# AMS_CLOCK.net
KiCad netlist of a schematic drawn in Altium Designer
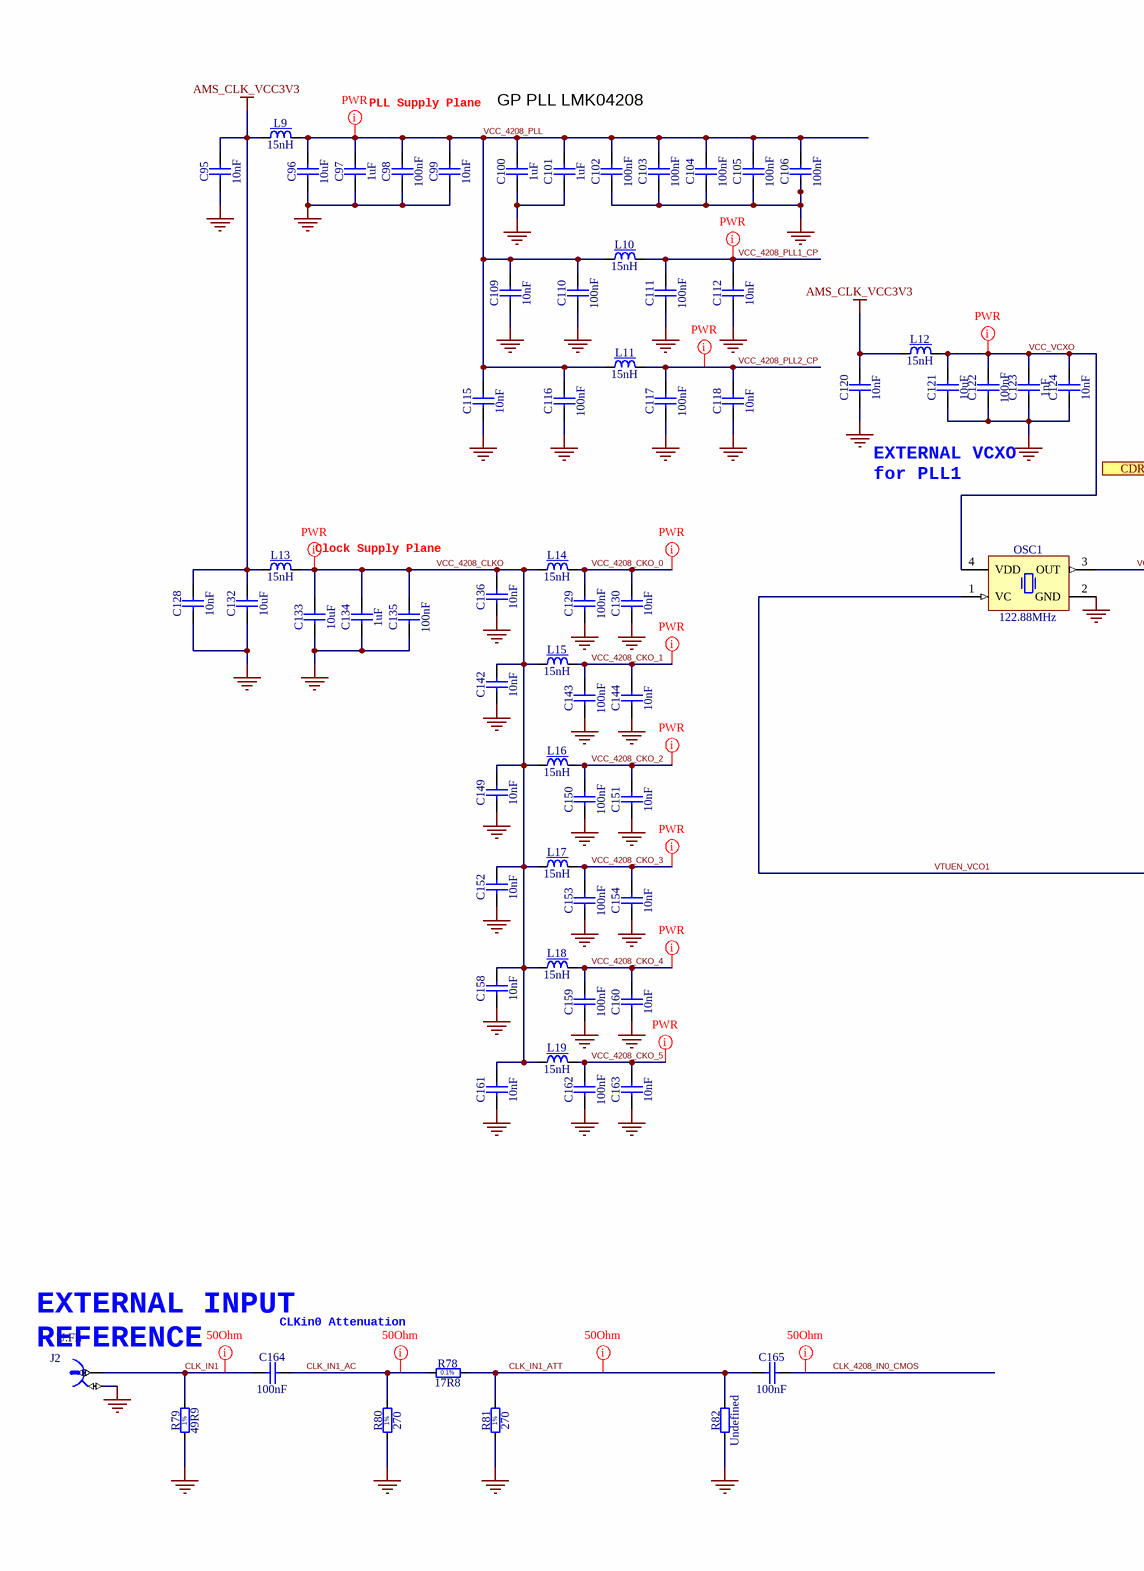
[diagram p0: AMS_CLOCK.SchDoc, left]
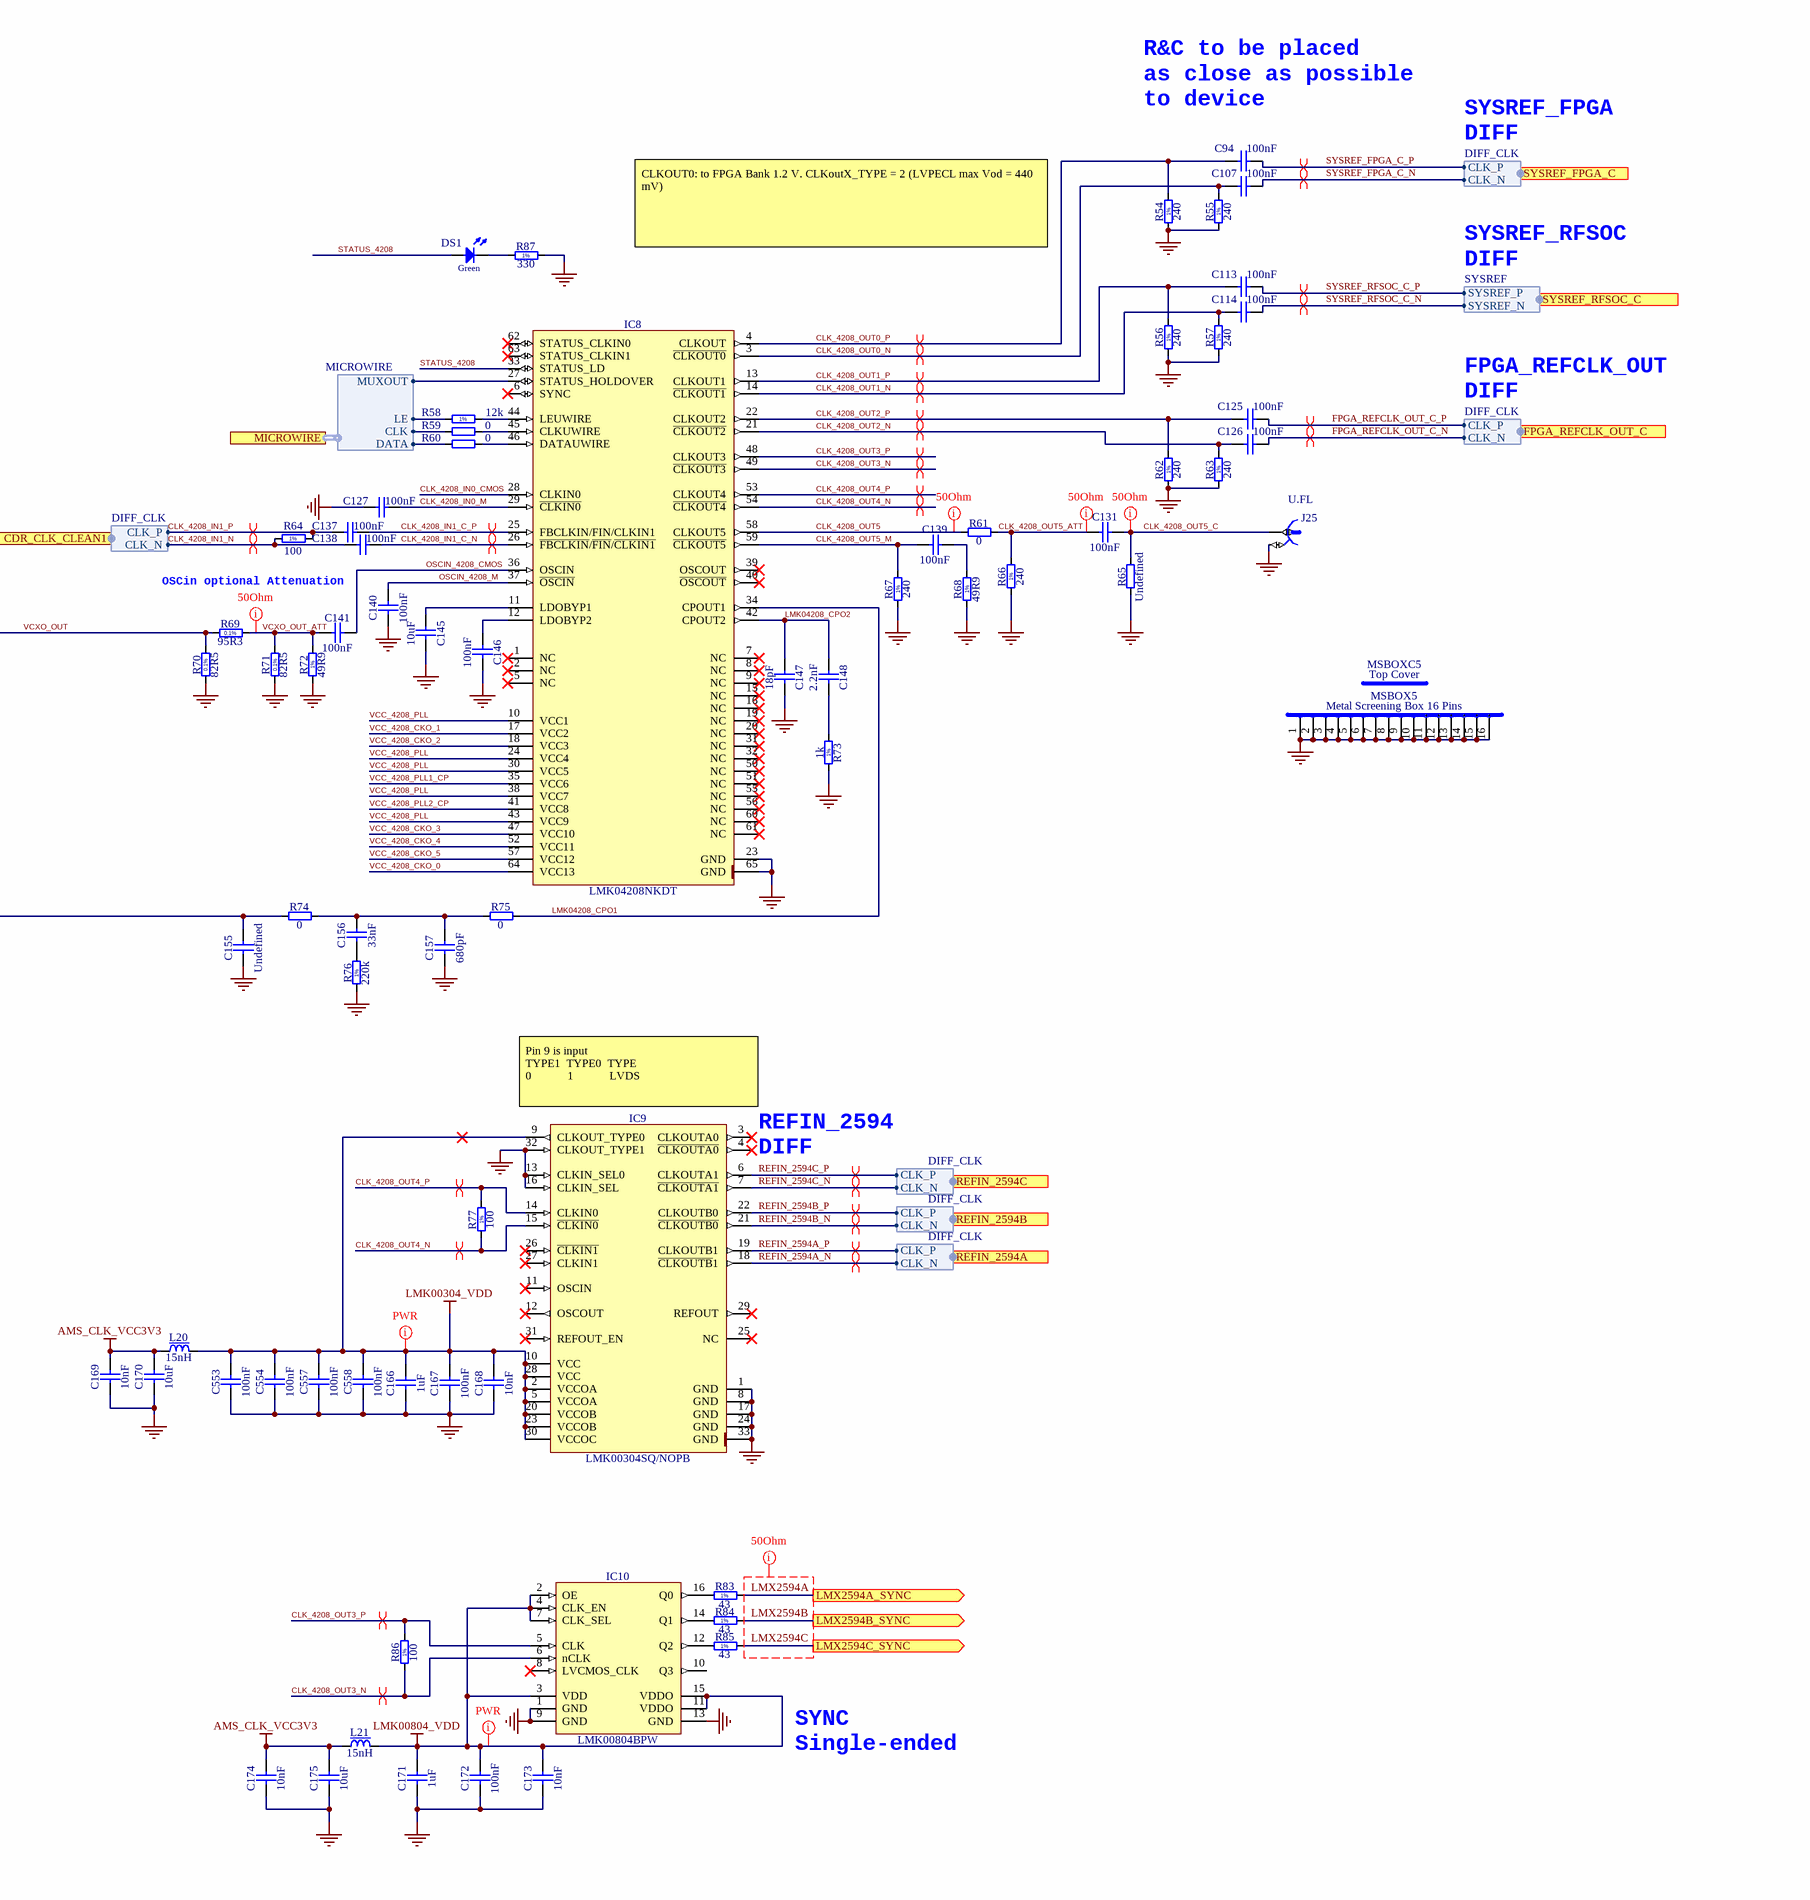
[diagram p1: AMS_CLOCK.SchDoc, right]

(export (version "E")
  (design (tool "Eeschema 10.0.6"))
  (components
    (comp (ref "C94")
      (value "100nF")
      (footprint "CAPC1005X55N")
      (description "Non-polarised capacitor")
      (fields
        (field (name "VOLTAGE") "25V")
        (field (name "TOLERANCE") "±10%")
        (field (name "AUTHOR") "CERN DEM JLC")
      )
      (libsource (lib "Capacitors") (part "Capacitor - non polarized"))
    )
    (comp (ref "C95")
      (value "10nF")
      (footprint "CAPC1005X55N")
      (description "Non-polarised capacitor")
      (fields
        (field (name "PART NUMBER") "CC0402_10NF_16V_10%_X7R")
        (field (name "VOLTAGE") "16V")
        (field (name "AUTHOR") "CERN DEM JLC")
      )
      (libsource (lib "Capacitors") (part "Capacitor - non polarized"))
    )
    (comp (ref "C96")
      (value "10uF")
      (footprint "CAPC1608X80N")
      (description "Non-polarised capacitor")
      (fields
        (field (name "PART NUMBER") "CC0603_10UF_10V_10%_X5R")
        (field (name "VOLTAGE") "10V")
        (field (name "AUTHOR") "CERN DEM JLC")
      )
      (libsource (lib "Capacitors") (part "Capacitor - non polarized"))
    )
    (comp (ref "C97")
      (value "1uF")
      (footprint "CAPC1005X55N")
      (description "Non-polarised capacitor")
      (fields
        (field (name "PART NUMBER") "CC0402_1UF_16V_10%_X5R")
        (field (name "VOLTAGE") "16V")
        (field (name "AUTHOR") "CERN DEM JLC")
      )
      (libsource (lib "Capacitors") (part "Capacitor - non polarized"))
    )
    (comp (ref "C98")
      (value "100nF")
      (footprint "CAPC1005X55N")
      (description "Non-polarised capacitor")
      (fields
        (field (name "PART NUMBER") "CC0402_100NF_25V_10%_X7R_YUDEN_TMK105B7104KVHF")
        (field (name "VOLTAGE") "25V")
        (field (name "AUTHOR") "CERN DEM JLC")
      )
      (libsource (lib "Capacitors") (part "Capacitor - non polarized"))
    )
    (comp (ref "C99")
      (value "10nF")
      (footprint "CAPC1005X55N")
      (description "Non-polarised capacitor")
      (fields
        (field (name "PART NUMBER") "CC0402_10NF_16V_10%_X7R")
        (field (name "VOLTAGE") "16V")
        (field (name "AUTHOR") "CERN DEM JLC")
      )
      (libsource (lib "Capacitors") (part "Capacitor - non polarized"))
    )
    (comp (ref "C100")
      (value "1uF")
      (footprint "CAPC1005X55N")
      (description "Non-polarised capacitor")
      (fields
        (field (name "VOLTAGE") "16V")
        (field (name "TOLERANCE") "±10%")
        (field (name "AUTHOR") "CERN DEM JLC")
      )
      (libsource (lib "Capacitors") (part "Capacitor - non polarized"))
    )
    (comp (ref "C101")
      (value "1uF")
      (footprint "CAPC1005X55N")
      (description "Non-polarised capacitor")
      (fields
        (field (name "VOLTAGE") "16V")
        (field (name "TOLERANCE") "±10%")
        (field (name "AUTHOR") "CERN DEM JLC")
      )
      (libsource (lib "Capacitors") (part "Capacitor - non polarized"))
    )
    (comp (ref "C102")
      (value "100nF")
      (footprint "CAPC1005X55N")
      (description "Non-polarised capacitor")
      (fields
        (field (name "VOLTAGE") "25V")
        (field (name "TOLERANCE") "±10%")
        (field (name "AUTHOR") "CERN DEM JLC")
      )
      (libsource (lib "Capacitors") (part "Capacitor - non polarized"))
    )
    (comp (ref "C103")
      (value "100nF")
      (footprint "CAPC1005X55N")
      (description "Non-polarised capacitor")
      (fields
        (field (name "VOLTAGE") "25V")
        (field (name "TOLERANCE") "±10%")
        (field (name "AUTHOR") "CERN DEM JLC")
      )
      (libsource (lib "Capacitors") (part "Capacitor - non polarized"))
    )
    (comp (ref "C104")
      (value "100nF")
      (footprint "CAPC1005X55N")
      (description "Non-polarised capacitor")
      (fields
        (field (name "VOLTAGE") "25V")
        (field (name "TOLERANCE") "±10%")
        (field (name "AUTHOR") "CERN DEM JLC")
      )
      (libsource (lib "Capacitors") (part "Capacitor - non polarized"))
    )
    (comp (ref "C105")
      (value "100nF")
      (footprint "CAPC1005X55N")
      (description "Non-polarised capacitor")
      (fields
        (field (name "VOLTAGE") "25V")
        (field (name "TOLERANCE") "±10%")
        (field (name "AUTHOR") "CERN DEM JLC")
      )
      (libsource (lib "Capacitors") (part "Capacitor - non polarized"))
    )
    (comp (ref "C106")
      (value "100nF")
      (footprint "CAPC1005X55N")
      (description "Non-polarised capacitor")
      (fields
        (field (name "VOLTAGE") "25V")
        (field (name "TOLERANCE") "±10%")
        (field (name "AUTHOR") "CERN DEM JLC")
      )
      (libsource (lib "Capacitors") (part "Capacitor - non polarized"))
    )
    (comp (ref "C107")
      (value "100nF")
      (footprint "CAPC1005X55N")
      (description "Non-polarised capacitor")
      (fields
        (field (name "VOLTAGE") "25V")
        (field (name "TOLERANCE") "±10%")
        (field (name "AUTHOR") "CERN DEM JLC")
      )
      (libsource (lib "Capacitors") (part "Capacitor - non polarized"))
    )
    (comp (ref "C109")
      (value "10nF")
      (footprint "CAPC1005X55N")
      (description "Non-polarised capacitor")
      (fields
        (field (name "VOLTAGE") "16V")
        (field (name "TOLERANCE") "±10%")
        (field (name "AUTHOR") "CERN DEM JLC")
      )
      (libsource (lib "Capacitors") (part "Capacitor - non polarized"))
    )
    (comp (ref "C110")
      (value "100nF")
      (footprint "CAPC1005X55N")
      (description "Non-polarised capacitor")
      (fields
        (field (name "VOLTAGE") "25V")
        (field (name "TOLERANCE") "±10%")
        (field (name "AUTHOR") "CERN DEM JLC")
      )
      (libsource (lib "Capacitors") (part "Capacitor - non polarized"))
    )
    (comp (ref "C111")
      (value "100nF")
      (footprint "CAPC1005X55N")
      (description "Non-polarised capacitor")
      (fields
        (field (name "VOLTAGE") "25V")
        (field (name "TOLERANCE") "±10%")
        (field (name "AUTHOR") "CERN DEM JLC")
      )
      (libsource (lib "Capacitors") (part "Capacitor - non polarized"))
    )
    (comp (ref "C112")
      (value "10nF")
      (footprint "CAPC1005X55N")
      (description "Non-polarised capacitor")
      (fields
        (field (name "VOLTAGE") "16V")
        (field (name "TOLERANCE") "±10%")
        (field (name "AUTHOR") "CERN DEM JLC")
      )
      (libsource (lib "Capacitors") (part "Capacitor - non polarized"))
    )
    (comp (ref "C113")
      (value "100nF")
      (footprint "CAPC1005X55N")
      (description "Non-polarised capacitor")
      (fields
        (field (name "VOLTAGE") "25V")
        (field (name "TOLERANCE") "±10%")
        (field (name "AUTHOR") "CERN DEM JLC")
      )
      (libsource (lib "Capacitors") (part "Capacitor - non polarized"))
    )
    (comp (ref "C114")
      (value "100nF")
      (footprint "CAPC1005X55N")
      (description "Non-polarised capacitor")
      (fields
        (field (name "VOLTAGE") "25V")
        (field (name "TOLERANCE") "±10%")
        (field (name "AUTHOR") "CERN DEM JLC")
      )
      (libsource (lib "Capacitors") (part "Capacitor - non polarized"))
    )
    (comp (ref "C115")
      (value "10nF")
      (footprint "CAPC1005X55N")
      (description "Non-polarised capacitor")
      (fields
        (field (name "VOLTAGE") "16V")
        (field (name "TOLERANCE") "±10%")
        (field (name "AUTHOR") "CERN DEM JLC")
      )
      (libsource (lib "Capacitors") (part "Capacitor - non polarized"))
    )
    (comp (ref "C116")
      (value "100nF")
      (footprint "CAPC1005X55N")
      (description "Non-polarised capacitor")
      (fields
        (field (name "VOLTAGE") "25V")
        (field (name "TOLERANCE") "±10%")
        (field (name "AUTHOR") "CERN DEM JLC")
      )
      (libsource (lib "Capacitors") (part "Capacitor - non polarized"))
    )
    (comp (ref "C117")
      (value "100nF")
      (footprint "CAPC1005X55N")
      (description "Non-polarised capacitor")
      (fields
        (field (name "VOLTAGE") "25V")
        (field (name "TOLERANCE") "±10%")
        (field (name "AUTHOR") "CERN DEM JLC")
      )
      (libsource (lib "Capacitors") (part "Capacitor - non polarized"))
    )
    (comp (ref "C118")
      (value "10nF")
      (footprint "CAPC1005X55N")
      (description "Non-polarised capacitor")
      (fields
        (field (name "VOLTAGE") "16V")
        (field (name "TOLERANCE") "±10%")
        (field (name "AUTHOR") "CERN DEM JLC")
      )
      (libsource (lib "Capacitors") (part "Capacitor - non polarized"))
    )
    (comp (ref "C120")
      (value "10nF")
      (footprint "CAPC1005X55N")
      (description "Non-polarised capacitor")
      (fields
        (field (name "VOLTAGE") "16V")
        (field (name "TOLERANCE") "±10%")
        (field (name "AUTHOR") "CERN DEM JLC")
      )
      (libsource (lib "Capacitors") (part "Capacitor - non polarized"))
    )
    (comp (ref "C121")
      (value "10uF")
      (footprint "CAPC1608X80N")
      (description "Non-polarised capacitor")
      (fields
        (field (name "VOLTAGE") "10V")
        (field (name "TOLERANCE") "±10%")
        (field (name "AUTHOR") "CERN DEM JLC")
      )
      (libsource (lib "Capacitors") (part "Capacitor - non polarized"))
    )
    (comp (ref "C122")
      (value "100nF")
      (footprint "CAPC1005X55N")
      (description "Non-polarised capacitor")
      (fields
        (field (name "VOLTAGE") "25V")
        (field (name "TOLERANCE") "±10%")
        (field (name "AUTHOR") "CERN DEM JLC")
      )
      (libsource (lib "Capacitors") (part "Capacitor - non polarized"))
    )
    (comp (ref "C123")
      (value "1nF")
      (footprint "CAPC1005X55N")
      (description "Non-polarised capacitor")
      (fields
        (field (name "PART NUMBER") "CC0402_1NF_50V_10%_X7R")
        (field (name "VOLTAGE") "50V")
        (field (name "AUTHOR") "CERN DEM JLC")
      )
      (libsource (lib "Capacitors") (part "Capacitor - non polarized"))
    )
    (comp (ref "C124")
      (value "10nF")
      (footprint "CAPC1005X55N")
      (description "Non-polarised capacitor")
      (fields
        (field (name "VOLTAGE") "16V")
        (field (name "TOLERANCE") "±10%")
        (field (name "AUTHOR") "CERN DEM JLC")
      )
      (libsource (lib "Capacitors") (part "Capacitor - non polarized"))
    )
    (comp (ref "C125")
      (value "100nF")
      (footprint "CAPC1005X55N")
      (description "Non-polarised capacitor")
      (fields
        (field (name "VOLTAGE") "25V")
        (field (name "TOLERANCE") "±10%")
        (field (name "AUTHOR") "CERN DEM JLC")
      )
      (libsource (lib "Capacitors") (part "Capacitor - non polarized"))
    )
    (comp (ref "C126")
      (value "100nF")
      (footprint "CAPC1005X55N")
      (description "Non-polarised capacitor")
      (fields
        (field (name "VOLTAGE") "25V")
        (field (name "TOLERANCE") "±10%")
        (field (name "AUTHOR") "CERN DEM JLC")
      )
      (libsource (lib "Capacitors") (part "Capacitor - non polarized"))
    )
    (comp (ref "C127")
      (value "100nF")
      (footprint "CAPC1005X55N")
      (description "Non-polarised capacitor")
      (fields
        (field (name "VOLTAGE") "25V")
        (field (name "TOLERANCE") "±10%")
        (field (name "AUTHOR") "CERN DEM JLC")
      )
      (libsource (lib "Capacitors") (part "Capacitor - non polarized"))
    )
    (comp (ref "C128")
      (value "10nF")
      (footprint "CAPC1005X55N")
      (description "Non-polarised capacitor")
      (fields
        (field (name "VOLTAGE") "16V")
        (field (name "TOLERANCE") "±10%")
        (field (name "AUTHOR") "CERN DEM JLC")
      )
      (libsource (lib "Capacitors") (part "Capacitor - non polarized"))
    )
    (comp (ref "C129")
      (value "100nF")
      (footprint "CAPC1005X55N")
      (description "Non-polarised capacitor")
      (fields
        (field (name "VOLTAGE") "25V")
        (field (name "TOLERANCE") "±10%")
        (field (name "AUTHOR") "CERN DEM JLC")
      )
      (libsource (lib "Capacitors") (part "Capacitor - non polarized"))
    )
    (comp (ref "C130")
      (value "10nF")
      (footprint "CAPC1005X55N")
      (description "Non-polarised capacitor")
      (fields
        (field (name "VOLTAGE") "16V")
        (field (name "TOLERANCE") "±10%")
        (field (name "AUTHOR") "CERN DEM JLC")
      )
      (libsource (lib "Capacitors") (part "Capacitor - non polarized"))
    )
    (comp (ref "C131")
      (value "100nF")
      (footprint "CAPC1005X55N")
      (description "Non-polarised capacitor")
      (fields
        (field (name "VOLTAGE") "25V")
        (field (name "TOLERANCE") "±10%")
        (field (name "AUTHOR") "CERN DEM JLC")
      )
      (libsource (lib "Capacitors") (part "Capacitor - non polarized"))
    )
    (comp (ref "C132")
      (value "10uF")
      (footprint "CAPC1608X80N")
      (description "Non-polarised capacitor")
      (fields
        (field (name "VOLTAGE") "10V")
        (field (name "TOLERANCE") "±10%")
        (field (name "AUTHOR") "CERN DEM JLC")
      )
      (libsource (lib "Capacitors") (part "Capacitor - non polarized"))
    )
    (comp (ref "C133")
      (value "10uF")
      (footprint "CAPC1608X80N")
      (description "Non-polarised capacitor")
      (fields
        (field (name "VOLTAGE") "10V")
        (field (name "TOLERANCE") "±10%")
        (field (name "AUTHOR") "CERN DEM JLC")
      )
      (libsource (lib "Capacitors") (part "Capacitor - non polarized"))
    )
    (comp (ref "C134")
      (value "1uF")
      (footprint "CAPC1005X55N")
      (description "Non-polarised capacitor")
      (fields
        (field (name "VOLTAGE") "16V")
        (field (name "TOLERANCE") "±10%")
        (field (name "AUTHOR") "CERN DEM JLC")
      )
      (libsource (lib "Capacitors") (part "Capacitor - non polarized"))
    )
    (comp (ref "C135")
      (value "100nF")
      (footprint "CAPC1005X55N")
      (description "Non-polarised capacitor")
      (fields
        (field (name "VOLTAGE") "25V")
        (field (name "TOLERANCE") "±10%")
        (field (name "AUTHOR") "CERN DEM JLC")
      )
      (libsource (lib "Capacitors") (part "Capacitor - non polarized"))
    )
    (comp (ref "C136")
      (value "10nF")
      (footprint "CAPC1005X55N")
      (description "Non-polarised capacitor")
      (fields
        (field (name "VOLTAGE") "16V")
        (field (name "TOLERANCE") "±10%")
        (field (name "AUTHOR") "CERN DEM JLC")
      )
      (libsource (lib "Capacitors") (part "Capacitor - non polarized"))
    )
    (comp (ref "C137")
      (value "100nF")
      (footprint "CAPC1005X55N")
      (description "Non-polarised capacitor")
      (fields
        (field (name "VOLTAGE") "25V")
        (field (name "TOLERANCE") "±10%")
        (field (name "AUTHOR") "CERN DEM JLC")
      )
      (libsource (lib "Capacitors") (part "Capacitor - non polarized"))
    )
    (comp (ref "C138")
      (value "100nF")
      (footprint "CAPC1005X55N")
      (description "Non-polarised capacitor")
      (fields
        (field (name "VOLTAGE") "25V")
        (field (name "TOLERANCE") "±10%")
        (field (name "AUTHOR") "CERN DEM JLC")
      )
      (libsource (lib "Capacitors") (part "Capacitor - non polarized"))
    )
    (comp (ref "C139")
      (value "100nF")
      (footprint "CAPC1005X55N")
      (description "Non-polarised capacitor")
      (fields
        (field (name "VOLTAGE") "25V")
        (field (name "TOLERANCE") "±10%")
        (field (name "AUTHOR") "CERN DEM JLC")
      )
      (libsource (lib "Capacitors") (part "Capacitor - non polarized"))
    )
    (comp (ref "C140")
      (value "100nF")
      (footprint "CAPC1005X55N")
      (description "Non-polarised capacitor")
      (fields
        (field (name "VOLTAGE") "25V")
        (field (name "TOLERANCE") "±10%")
        (field (name "AUTHOR") "CERN DEM JLC")
      )
      (libsource (lib "Capacitors") (part "Capacitor - non polarized"))
    )
    (comp (ref "C141")
      (value "100nF")
      (footprint "CAPC1005X55N")
      (description "Non-polarised capacitor")
      (fields
        (field (name "VOLTAGE") "25V")
        (field (name "TOLERANCE") "±10%")
        (field (name "AUTHOR") "CERN DEM JLC")
      )
      (libsource (lib "Capacitors") (part "Capacitor - non polarized"))
    )
    (comp (ref "C142")
      (value "10nF")
      (footprint "CAPC1005X55N")
      (description "Non-polarised capacitor")
      (fields
        (field (name "VOLTAGE") "16V")
        (field (name "TOLERANCE") "±10%")
        (field (name "AUTHOR") "CERN DEM JLC")
      )
      (libsource (lib "Capacitors") (part "Capacitor - non polarized"))
    )
    (comp (ref "C143")
      (value "100nF")
      (footprint "CAPC1005X55N")
      (description "Non-polarised capacitor")
      (fields
        (field (name "VOLTAGE") "25V")
        (field (name "TOLERANCE") "±10%")
        (field (name "AUTHOR") "CERN DEM JLC")
      )
      (libsource (lib "Capacitors") (part "Capacitor - non polarized"))
    )
    (comp (ref "C144")
      (value "10nF")
      (footprint "CAPC1005X55N")
      (description "Non-polarised capacitor")
      (fields
        (field (name "VOLTAGE") "16V")
        (field (name "TOLERANCE") "±10%")
        (field (name "AUTHOR") "CERN DEM JLC")
      )
      (libsource (lib "Capacitors") (part "Capacitor - non polarized"))
    )
    (comp (ref "C145")
      (value "10uF")
      (footprint "CAPC1608X80N")
      (description "Non-polarised capacitor")
      (fields
        (field (name "VOLTAGE") "10V")
        (field (name "TOLERANCE") "±10%")
        (field (name "AUTHOR") "CERN DEM JLC")
      )
      (libsource (lib "Capacitors") (part "Capacitor - non polarized"))
    )
    (comp (ref "C146")
      (value "100nF")
      (footprint "CAPC1005X55N")
      (description "Non-polarised capacitor")
      (fields
        (field (name "VOLTAGE") "25V")
        (field (name "TOLERANCE") "±10%")
        (field (name "AUTHOR") "CERN DEM JLC")
      )
      (libsource (lib "Capacitors") (part "Capacitor - non polarized"))
    )
    (comp (ref "C147")
      (value "18pF")
      (footprint "CAPC1005X55N")
      (description "Non-polarised capacitor")
      (fields
        (field (name "PART NUMBER") "CC0402_18PF_50V_5%_C0G")
        (field (name "VOLTAGE") "50V")
        (field (name "AUTHOR") "CERN DEM JLC")
      )
      (libsource (lib "Capacitors") (part "Capacitor - non polarized"))
    )
    (comp (ref "C148")
      (value "2.2nF")
      (footprint "CAPC1005X55N")
      (description "Non-polarised capacitor")
      (fields
        (field (name "PART NUMBER") "CC0402_2.2NF_50V_10%_X7R")
        (field (name "VOLTAGE") "50V")
        (field (name "AUTHOR") "CERN DEM JLC")
      )
      (libsource (lib "Capacitors") (part "Capacitor - non polarized"))
    )
    (comp (ref "C149")
      (value "10nF")
      (footprint "CAPC1005X55N")
      (description "Non-polarised capacitor")
      (fields
        (field (name "VOLTAGE") "16V")
        (field (name "TOLERANCE") "±10%")
        (field (name "AUTHOR") "CERN DEM JLC")
      )
      (libsource (lib "Capacitors") (part "Capacitor - non polarized"))
    )
    (comp (ref "C150")
      (value "100nF")
      (footprint "CAPC1005X55N")
      (description "Non-polarised capacitor")
      (fields
        (field (name "VOLTAGE") "25V")
        (field (name "TOLERANCE") "±10%")
        (field (name "AUTHOR") "CERN DEM JLC")
      )
      (libsource (lib "Capacitors") (part "Capacitor - non polarized"))
    )
    (comp (ref "C151")
      (value "10nF")
      (footprint "CAPC1005X55N")
      (description "Non-polarised capacitor")
      (fields
        (field (name "VOLTAGE") "16V")
        (field (name "TOLERANCE") "±10%")
        (field (name "AUTHOR") "CERN DEM JLC")
      )
      (libsource (lib "Capacitors") (part "Capacitor - non polarized"))
    )
    (comp (ref "C152")
      (value "10nF")
      (footprint "CAPC1005X55N")
      (description "Non-polarised capacitor")
      (fields
        (field (name "VOLTAGE") "16V")
        (field (name "TOLERANCE") "±10%")
        (field (name "AUTHOR") "CERN DEM JLC")
      )
      (libsource (lib "Capacitors") (part "Capacitor - non polarized"))
    )
    (comp (ref "C153")
      (value "100nF")
      (footprint "CAPC1005X55N")
      (description "Non-polarised capacitor")
      (fields
        (field (name "VOLTAGE") "25V")
        (field (name "TOLERANCE") "±10%")
        (field (name "AUTHOR") "CERN DEM JLC")
      )
      (libsource (lib "Capacitors") (part "Capacitor - non polarized"))
    )
    (comp (ref "C154")
      (value "10nF")
      (footprint "CAPC1005X55N")
      (description "Non-polarised capacitor")
      (fields
        (field (name "VOLTAGE") "16V")
        (field (name "TOLERANCE") "±10%")
        (field (name "AUTHOR") "CERN DEM JLC")
      )
      (libsource (lib "Capacitors") (part "Capacitor - non polarized"))
    )
    (comp (ref "C155")
      (value "Undefined")
      (footprint "CAPC1005X55N")
      (description "Non-polarised capacitor")
      (fields (field (name "PART NUMBER") "CC0402_NO-VALUE") (field (name "AUTHOR") "CERN DEM JLC"))
      (libsource (lib "Capacitors") (part "Capacitor - non polarized"))
    )
    (comp (ref "C156")
      (value "33nF")
      (footprint "CAPC1608X87N")
      (description "Non-polarised capacitor")
      (fields
        (field (name "VOLTAGE") "25V")
        (field (name "TOLERANCE") "±10%")
        (field (name "AUTHOR") "CERN DEM JLC")
      )
      (libsource (lib "Capacitors") (part "Capacitor - non polarized"))
    )
    (comp (ref "C157")
      (value "680pF")
      (footprint "CAPC1005X55N")
      (description "Non-polarised capacitor")
      (fields
        (field (name "PART NUMBER") "CC0402_680PF_50V_5%_X7R")
        (field (name "VOLTAGE") "50V")
        (field (name "AUTHOR") "CERN DEM JLC")
      )
      (libsource (lib "Capacitors") (part "Capacitor - non polarized"))
    )
    (comp (ref "C158")
      (value "10nF")
      (footprint "CAPC1005X55N")
      (description "Non-polarised capacitor")
      (fields
        (field (name "VOLTAGE") "16V")
        (field (name "TOLERANCE") "±10%")
        (field (name "AUTHOR") "CERN DEM JLC")
      )
      (libsource (lib "Capacitors") (part "Capacitor - non polarized"))
    )
    (comp (ref "C159")
      (value "100nF")
      (footprint "CAPC1005X55N")
      (description "Non-polarised capacitor")
      (fields
        (field (name "VOLTAGE") "25V")
        (field (name "TOLERANCE") "±10%")
        (field (name "AUTHOR") "CERN DEM JLC")
      )
      (libsource (lib "Capacitors") (part "Capacitor - non polarized"))
    )
    (comp (ref "C160")
      (value "10nF")
      (footprint "CAPC1005X55N")
      (description "Non-polarised capacitor")
      (fields
        (field (name "VOLTAGE") "16V")
        (field (name "TOLERANCE") "±10%")
        (field (name "AUTHOR") "CERN DEM JLC")
      )
      (libsource (lib "Capacitors") (part "Capacitor - non polarized"))
    )
    (comp (ref "C161")
      (value "10nF")
      (footprint "CAPC1005X55N")
      (description "Non-polarised capacitor")
      (fields
        (field (name "VOLTAGE") "16V")
        (field (name "TOLERANCE") "±10%")
        (field (name "AUTHOR") "CERN DEM JLC")
      )
      (libsource (lib "Capacitors") (part "Capacitor - non polarized"))
    )
    (comp (ref "C162")
      (value "100nF")
      (footprint "CAPC1005X55N")
      (description "Non-polarised capacitor")
      (fields
        (field (name "VOLTAGE") "25V")
        (field (name "TOLERANCE") "±10%")
        (field (name "AUTHOR") "CERN DEM JLC")
      )
      (libsource (lib "Capacitors") (part "Capacitor - non polarized"))
    )
    (comp (ref "C163")
      (value "10nF")
      (footprint "CAPC1005X55N")
      (description "Non-polarised capacitor")
      (fields
        (field (name "VOLTAGE") "16V")
        (field (name "TOLERANCE") "±10%")
        (field (name "AUTHOR") "CERN DEM JLC")
      )
      (libsource (lib "Capacitors") (part "Capacitor - non polarized"))
    )
    (comp (ref "C164")
      (value "100nF")
      (footprint "CAPC1005X55N")
      (description "Non-polarised capacitor")
      (fields
        (field (name "VOLTAGE") "25V")
        (field (name "TOLERANCE") "±10%")
        (field (name "AUTHOR") "CERN DEM JLC")
      )
      (libsource (lib "Capacitors") (part "Capacitor - non polarized"))
    )
    (comp (ref "C165")
      (value "100nF")
      (footprint "CAPC1005X55N")
      (description "Non-polarised capacitor")
      (fields
        (field (name "VOLTAGE") "25V")
        (field (name "TOLERANCE") "±10%")
        (field (name "AUTHOR") "CERN DEM JLC")
      )
      (libsource (lib "Capacitors") (part "Capacitor - non polarized"))
    )
    (comp (ref "C166")
      (value "1uF")
      (footprint "CAPC1005X55N")
      (description "Non-polarised capacitor")
      (fields
        (field (name "VOLTAGE") "16V")
        (field (name "TOLERANCE") "±10%")
        (field (name "AUTHOR") "CERN DEM JLC")
      )
      (libsource (lib "Capacitors") (part "Capacitor - non polarized"))
    )
    (comp (ref "C167")
      (value "100nF")
      (footprint "CAPC1005X55N")
      (description "Non-polarised capacitor")
      (fields
        (field (name "VOLTAGE") "25V")
        (field (name "TOLERANCE") "±10%")
        (field (name "AUTHOR") "CERN DEM JLC")
      )
      (libsource (lib "Capacitors") (part "Capacitor - non polarized"))
    )
    (comp (ref "C168")
      (value "10nF")
      (footprint "CAPC1005X55N")
      (description "Non-polarised capacitor")
      (fields
        (field (name "VOLTAGE") "16V")
        (field (name "TOLERANCE") "±10%")
        (field (name "AUTHOR") "CERN DEM JLC")
      )
      (libsource (lib "Capacitors") (part "Capacitor - non polarized"))
    )
    (comp (ref "C169")
      (value "10nF")
      (footprint "CAPC1005X55N")
      (description "Non-polarised capacitor")
      (fields
        (field (name "VOLTAGE") "16V")
        (field (name "TOLERANCE") "±10%")
        (field (name "AUTHOR") "CERN DEM JLC")
      )
      (libsource (lib "Capacitors") (part "Capacitor - non polarized"))
    )
    (comp (ref "C170")
      (value "10uF")
      (footprint "CAPC1608X80N")
      (description "Non-polarised capacitor")
      (fields
        (field (name "VOLTAGE") "10V")
        (field (name "TOLERANCE") "±10%")
        (field (name "AUTHOR") "CERN DEM JLC")
      )
      (libsource (lib "Capacitors") (part "Capacitor - non polarized"))
    )
    (comp (ref "C171")
      (value "1uF")
      (footprint "CAPC1005X55N")
      (description "Non-polarised capacitor")
      (fields
        (field (name "VOLTAGE") "16V")
        (field (name "TOLERANCE") "±10%")
        (field (name "AUTHOR") "CERN DEM JLC")
      )
      (libsource (lib "Capacitors") (part "Capacitor - non polarized"))
    )
    (comp (ref "C172")
      (value "100nF")
      (footprint "CAPC1005X55N")
      (description "Non-polarised capacitor")
      (fields
        (field (name "VOLTAGE") "25V")
        (field (name "TOLERANCE") "±10%")
        (field (name "AUTHOR") "CERN DEM JLC")
      )
      (libsource (lib "Capacitors") (part "Capacitor - non polarized"))
    )
    (comp (ref "C173")
      (value "10nF")
      (footprint "CAPC1005X55N")
      (description "Non-polarised capacitor")
      (fields
        (field (name "VOLTAGE") "16V")
        (field (name "TOLERANCE") "±10%")
        (field (name "AUTHOR") "CERN DEM JLC")
      )
      (libsource (lib "Capacitors") (part "Capacitor - non polarized"))
    )
    (comp (ref "C174")
      (value "10nF")
      (footprint "CAPC1005X55N")
      (description "Non-polarised capacitor")
      (fields
        (field (name "VOLTAGE") "16V")
        (field (name "TOLERANCE") "±10%")
        (field (name "AUTHOR") "CERN DEM JLC")
      )
      (libsource (lib "Capacitors") (part "Capacitor - non polarized"))
    )
    (comp (ref "C175")
      (value "10uF")
      (footprint "CAPC1608X80N")
      (description "Non-polarised capacitor")
      (fields
        (field (name "VOLTAGE") "10V")
        (field (name "TOLERANCE") "±10%")
        (field (name "AUTHOR") "CERN DEM JLC")
      )
      (libsource (lib "Capacitors") (part "Capacitor - non polarized"))
    )
    (comp (ref "C553")
      (value "100nF")
      (footprint "CAPC1005X55N")
      (description "Non-polarised capacitor")
      (fields
        (field (name "VOLTAGE") "25V")
        (field (name "TOLERANCE") "±10%")
        (field (name "AUTHOR") "CERN DEM JLC")
      )
      (libsource (lib "Capacitors") (part "Capacitor - non polarized"))
    )
    (comp (ref "C554")
      (value "100nF")
      (footprint "CAPC1005X55N")
      (description "Non-polarised capacitor")
      (fields
        (field (name "VOLTAGE") "25V")
        (field (name "TOLERANCE") "±10%")
        (field (name "AUTHOR") "CERN DEM JLC")
      )
      (libsource (lib "Capacitors") (part "Capacitor - non polarized"))
    )
    (comp (ref "C557")
      (value "100nF")
      (footprint "CAPC1005X55N")
      (description "Non-polarised capacitor")
      (fields
        (field (name "VOLTAGE") "25V")
        (field (name "TOLERANCE") "±10%")
        (field (name "AUTHOR") "CERN DEM JLC")
      )
      (libsource (lib "Capacitors") (part "Capacitor - non polarized"))
    )
    (comp (ref "C558")
      (value "100nF")
      (footprint "CAPC1005X55N")
      (description "Non-polarised capacitor")
      (fields
        (field (name "VOLTAGE") "25V")
        (field (name "TOLERANCE") "±10%")
        (field (name "AUTHOR") "CERN DEM JLC")
      )
      (libsource (lib "Capacitors") (part "Capacitor - non polarized"))
    )
    (comp (ref "DS1")
      (value "Green")
      (footprint "LED_OSRAM_LGL29K")
      (description "LED Green 1C 2A")
      (fields
        (field (name "PART NUMBER") "LED_OSRAM_LG L29K-G2J1-24-Z")
        (field (name "MANUFACTURER") "OSRAM")
        (field (name "AUTHOR") "CERN DEM JLC")
      )
      (libsource (lib "ICs And Semiconductors") (part "LED Green 1C 2A"))
    )
    (comp (ref "IC8")
      (value "LMK04208NKDT")
      (footprint "QFN50P900X900X80-65N-S730")
      (description "Low-Noise Clock Jitter Cleaner with Dual Loop PLLs")
      (fields (field (name "MANUFACTURER") "TEXAS INSTRUMENTS") (field (name "AUTHOR") "CERN DEM JLC"))
      (libsource (lib "ICs And Semiconductors") (part "LMK04208"))
    )
    (comp (ref "IC9")
      (value "LMK00304SQ/NOPB")
      (footprint "QFN50P500X500X80-33N-S320")
      (description "3-GHz 4-Output Ultra-Low Additive Jitter Differential Clock Buffer/Level Translator")
      (fields (field (name "MANUFACTURER") "TEXAS INSTRUMENTS") (field (name "AUTHOR") "CERN DEM JLC"))
      (libsource (lib "ICs And Semiconductors") (part "LMK00304"))
    )
    (comp (ref "IC10")
      (value "LMK00804BPW")
      (footprint "SOP65P640X120-16N")
      (description "Low Skew, 1-to-4 Multiplexed Differential/LVCMOS-to-LVCMOS/TTL Fanout Buffer")
      (fields (field (name "MANUFACTURER") "TEXAS INSTRUMENTS") (field (name "AUTHOR") "CERN DEM JLC"))
      (libsource (lib "ICs And Semiconductors") (part "LMK00804B"))
    )
    (comp (ref "J2")
      (value "U.FL")
      (footprint "HIROSE_U.FL-R-SMT-1(10)")
      (fields
        (field (name "MANUFACTURER PART NUMBER") "U.FL-R-SMT-1(10)")
        (field (name "MANUFACTURER") "HIROSE (HRS)")
        (field (name "PART NUMBER") "HIROSE_U.FL-R-SMT-1(10)")
        (field (name "AUTHOR") "CERN DEM JLC")
      )
      (libsource (lib "") (part "Coax_1Male_1Shield_1"))
    )
    (comp (ref "J25")
      (value "U.FL")
      (footprint "HIROSE_U.FL-R-SMT-1(10)")
      (fields
        (field (name "MANUFACTURER PART NUMBER") "U.FL-R-SMT-1(10)")
        (field (name "MANUFACTURER") "HIROSE (HRS)")
        (field (name "PART NUMBER") "HIROSE_U.FL-R-SMT-1(10)")
        (field (name "AUTHOR") "CERN DEM JLC")
      )
      (libsource (lib "Connectors") (part "Coax_1Male_1Shield"))
    )
    (comp (ref "L9")
      (value "15nH")
      (footprint "IND_COILCRAFT_0402DC")
      (description "Inductor With Core")
      (fields
        (field (name "PART NUMBER") "IND0402_15NH_2%_COILCRAFT_0402DC")
        (field (name "POWER") "1A")
        (field (name "AUTHOR") "CERN DEM JLC")
      )
      (libsource (lib "Inductors & Transformers") (part "Inductor With Magnetic core"))
    )
    (comp (ref "L10")
      (value "15nH")
      (footprint "IND_COILCRAFT_0402DC")
      (description "Inductor With Core")
      (fields
        (field (name "TOLERANCE") "±2%")
        (field (name "PART NUMBER") "IND0402_15NH_2%_COILCRAFT_0402DC")
        (field (name "AUTHOR") "CERN DEM JLC")
      )
      (libsource (lib "Inductors & Transformers") (part "Inductor With Magnetic core"))
    )
    (comp (ref "L11")
      (value "15nH")
      (footprint "IND_COILCRAFT_0402DC")
      (description "Inductor With Core")
      (fields
        (field (name "TOLERANCE") "±2%")
        (field (name "PART NUMBER") "IND0402_15NH_2%_COILCRAFT_0402DC")
        (field (name "AUTHOR") "CERN DEM JLC")
      )
      (libsource (lib "Inductors & Transformers") (part "Inductor With Magnetic core"))
    )
    (comp (ref "L12")
      (value "15nH")
      (footprint "IND_COILCRAFT_0402DC")
      (description "Inductor With Core")
      (fields
        (field (name "TOLERANCE") "±2%")
        (field (name "PART NUMBER") "IND0402_15NH_2%_COILCRAFT_0402DC")
        (field (name "AUTHOR") "CERN DEM JLC")
      )
      (libsource (lib "Inductors & Transformers") (part "Inductor With Magnetic core"))
    )
    (comp (ref "L13")
      (value "15nH")
      (footprint "IND_COILCRAFT_0402DC")
      (description "Inductor With Core")
      (fields
        (field (name "TOLERANCE") "±2%")
        (field (name "PART NUMBER") "IND0402_15NH_2%_COILCRAFT_0402DC")
        (field (name "AUTHOR") "CERN DEM JLC")
      )
      (libsource (lib "Inductors & Transformers") (part "Inductor With Magnetic core"))
    )
    (comp (ref "L14")
      (value "15nH")
      (footprint "IND_COILCRAFT_0402DC")
      (description "Inductor With Core")
      (fields
        (field (name "TOLERANCE") "±2%")
        (field (name "PART NUMBER") "IND0402_15NH_2%_COILCRAFT_0402DC")
        (field (name "AUTHOR") "CERN DEM JLC")
      )
      (libsource (lib "Inductors & Transformers") (part "Inductor With Magnetic core"))
    )
    (comp (ref "L15")
      (value "15nH")
      (footprint "IND_COILCRAFT_0402DC")
      (description "Inductor With Core")
      (fields
        (field (name "TOLERANCE") "±2%")
        (field (name "PART NUMBER") "IND0402_15NH_2%_COILCRAFT_0402DC")
        (field (name "AUTHOR") "CERN DEM JLC")
      )
      (libsource (lib "Inductors & Transformers") (part "Inductor With Magnetic core"))
    )
    (comp (ref "L16")
      (value "15nH")
      (footprint "IND_COILCRAFT_0402DC")
      (description "Inductor With Core")
      (fields
        (field (name "TOLERANCE") "±2%")
        (field (name "PART NUMBER") "IND0402_15NH_2%_COILCRAFT_0402DC")
        (field (name "AUTHOR") "CERN DEM JLC")
      )
      (libsource (lib "Inductors & Transformers") (part "Inductor With Magnetic core"))
    )
    (comp (ref "L17")
      (value "15nH")
      (footprint "IND_COILCRAFT_0402DC")
      (description "Inductor With Core")
      (fields
        (field (name "TOLERANCE") "±2%")
        (field (name "PART NUMBER") "IND0402_15NH_2%_COILCRAFT_0402DC")
        (field (name "AUTHOR") "CERN DEM JLC")
      )
      (libsource (lib "Inductors & Transformers") (part "Inductor With Magnetic core"))
    )
    (comp (ref "L18")
      (value "15nH")
      (footprint "IND_COILCRAFT_0402DC")
      (description "Inductor With Core")
      (fields
        (field (name "TOLERANCE") "±2%")
        (field (name "PART NUMBER") "IND0402_15NH_2%_COILCRAFT_0402DC")
        (field (name "AUTHOR") "CERN DEM JLC")
      )
      (libsource (lib "Inductors & Transformers") (part "Inductor With Magnetic core"))
    )
    (comp (ref "L19")
      (value "15nH")
      (footprint "IND_COILCRAFT_0402DC")
      (description "Inductor With Core")
      (fields
        (field (name "TOLERANCE") "±2%")
        (field (name "PART NUMBER") "IND0402_15NH_2%_COILCRAFT_0402DC")
        (field (name "AUTHOR") "CERN DEM JLC")
      )
      (libsource (lib "Inductors & Transformers") (part "Inductor With Magnetic core"))
    )
    (comp (ref "L20")
      (value "15nH")
      (footprint "IND_COILCRAFT_0402DC")
      (description "Inductor With Core")
      (fields
        (field (name "TOLERANCE") "±2%")
        (field (name "PART NUMBER") "IND0402_15NH_2%_COILCRAFT_0402DC")
        (field (name "AUTHOR") "CERN DEM JLC")
      )
      (libsource (lib "Inductors & Transformers") (part "Inductor With Magnetic core"))
    )
    (comp (ref "L21")
      (value "15nH")
      (footprint "IND_COILCRAFT_0402DC")
      (description "Inductor With Core")
      (fields
        (field (name "TOLERANCE") "±2%")
        (field (name "PART NUMBER") "IND0402_15NH_2%_COILCRAFT_0402DC")
        (field (name "AUTHOR") "CERN DEM JLC")
      )
      (libsource (lib "Inductors & Transformers") (part "Inductor With Magnetic core"))
    )
    (comp (ref "MSBOX5")
      (value "Metal Screening Box 16 Pins")
      (footprint "MSBOX_LEADERTECH_SMS-254-F")
      (fields
        (field (name "PART NUMBER") "MSBOX_LEADERTECH_SMS-254-F")
        (field (name "MANUFACTURER") "LEADERTECH")
        (field (name "MANUFACTURER PART NUMBER") "SMS-254-F")
        (field (name "AUTHOR") "CERN DEM BC")
      )
      (libsource (lib "Eletro-mechanical") (part "Metal Screening Box - 16 pins"))
    )
    (comp (ref "MSBOXC5")
      (value "Top Cover")
      (footprint "MSBOX_LEADERTECH_SMS-254-C")
      (description "Metal Screening Box - Top Cover 0 Pin")
      (fields
        (field (name "PART NUMBER") "MSBOX_LEADERTECH_SMS-254-C")
        (field (name "MANUFACTURER") "LEADERTECH")
        (field (name "AUTHOR") "CERN DEM BC")
      )
      (libsource (lib "Eletro-mechanical") (part "Metal Screening Box - Top Cover"))
    )
    (comp (ref "OSC1")
      (value "122.88MHz")
      (footprint "OSC_CRYSTEK_CVHD-950")
      (description "Oscillator 4 pins 1=VC 2=GND 3=OUT 4=VDD")
      (fields
        (field (name "PART NUMBER") "OSC_122.88MHZ_CRYSTEK_CVHD-950-122.880")
        (field (name "MANUFACTURER") "CRYSTEK CRYSTAL")
        (field (name "AUTHOR") "CERN DEM JLC")
      )
      (libsource (lib "ICs And Semiconductors") (part "Oscillator 1VC 2GND 3OUT 4VDD"))
    )
    (comp (ref "R54")
      (value "240")
      (footprint "RESC1005X40N")
      (description "Resistor - 1%")
      (fields
        (field (name "POWER") "0.0625W")
        (field (name "TOLERANCE") "±1%")
        (field (name "AUTHOR") "CERN DEM JLC")
      )
      (libsource (lib "Resistors") (part "Resistor - 1%"))
    )
    (comp (ref "R55")
      (value "240")
      (footprint "RESC1005X40N")
      (description "Resistor - 1%")
      (fields
        (field (name "POWER") "0.0625W")
        (field (name "TOLERANCE") "±1%")
        (field (name "AUTHOR") "CERN DEM JLC")
      )
      (libsource (lib "Resistors") (part "Resistor - 1%"))
    )
    (comp (ref "R56")
      (value "240")
      (footprint "RESC1005X40N")
      (description "Resistor - 1%")
      (fields
        (field (name "TOLERANCE") "±1%")
        (field (name "POWER") "0.0625W")
        (field (name "AUTHOR") "CERN DEM JLC")
      )
      (libsource (lib "Resistors") (part "Resistor - 1%"))
    )
    (comp (ref "R57")
      (value "240")
      (footprint "RESC1005X40N")
      (description "Resistor - 1%")
      (fields
        (field (name "TOLERANCE") "±1%")
        (field (name "POWER") "0.0625W")
        (field (name "AUTHOR") "CERN DEM JLC")
      )
      (libsource (lib "Resistors") (part "Resistor - 1%"))
    )
    (comp (ref "R58")
      (value "12k")
      (footprint "RESC1005X40N")
      (description "Resistor - 1%")
      (fields
        (field (name "PART NUMBER") "R0402_12K_1%_0.0625W_100PPM")
        (field (name "POWER") "0.0625W")
        (field (name "AUTHOR") "CERN DEM JLC")
      )
      (libsource (lib "Resistors") (part "Resistor - 1%"))
    )
    (comp (ref "R59")
      (value "0")
      (footprint "RESC1005X40N")
      (description "Resistor")
      (fields
        (field (name "PART NUMBER") "R0402_0R_JUMPER")
        (field (name "MANUFACTURER") "GENERIC")
        (field (name "AUTHOR") "CERN DEM JLC")
      )
      (libsource (lib "Resistors") (part "Resistor"))
    )
    (comp (ref "R60")
      (value "0")
      (footprint "RESC1005X40N")
      (description "Resistor")
      (fields
        (field (name "PART NUMBER") "R0402_0R_JUMPER")
        (field (name "MANUFACTURER") "GENERIC")
        (field (name "AUTHOR") "CERN DEM JLC")
      )
      (libsource (lib "Resistors") (part "Resistor"))
    )
    (comp (ref "R61")
      (value "0")
      (footprint "RESC1005X40N")
      (description "Resistor")
      (fields
        (field (name "PART NUMBER") "R0402_0R_JUMPER")
        (field (name "MANUFACTURER") "GENERIC")
        (field (name "AUTHOR") "CERN DEM JLC")
      )
      (libsource (lib "Resistors") (part "Resistor"))
    )
    (comp (ref "R62")
      (value "240")
      (footprint "RESC1005X40N")
      (description "Resistor - 1%")
      (fields
        (field (name "TOLERANCE") "±1%")
        (field (name "POWER") "0.0625W")
        (field (name "AUTHOR") "CERN DEM JLC")
      )
      (libsource (lib "Resistors") (part "Resistor - 1%"))
    )
    (comp (ref "R63")
      (value "240")
      (footprint "RESC1005X40N")
      (description "Resistor - 1%")
      (fields
        (field (name "TOLERANCE") "±1%")
        (field (name "POWER") "0.0625W")
        (field (name "AUTHOR") "CERN DEM JLC")
      )
      (libsource (lib "Resistors") (part "Resistor - 1%"))
    )
    (comp (ref "R64")
      (value "100")
      (footprint "RESC1005X40N")
      (description "Resistor - 1%")
      (fields
        (field (name "PART NUMBER") "R0402_100R_1%_0.0625W_100PPM")
        (field (name "POWER") "0.0625W")
        (field (name "AUTHOR") "CERN DEM JLC")
      )
      (libsource (lib "Resistors") (part "Resistor - 1%"))
    )
    (comp (ref "R65")
      (value "Undefined")
      (footprint "RESC1005X40N")
      (description "Resistor")
      (fields (field (name "PART NUMBER") "R0402_NO-VALUE") (field (name "AUTHOR") "CERN DEM JLC"))
      (libsource (lib "Resistors") (part "Resistor"))
    )
    (comp (ref "R66")
      (value "240")
      (footprint "RESC1005X40N")
      (description "Resistor - 1%")
      (fields
        (field (name "TOLERANCE") "±1%")
        (field (name "POWER") "0.0625W")
        (field (name "AUTHOR") "CERN DEM JLC")
      )
      (libsource (lib "Resistors") (part "Resistor - 1%"))
    )
    (comp (ref "R67")
      (value "240")
      (footprint "RESC1005X40N")
      (description "Resistor - 1%")
      (fields
        (field (name "TOLERANCE") "±1%")
        (field (name "POWER") "0.0625W")
        (field (name "AUTHOR") "CERN DEM JLC")
      )
      (libsource (lib "Resistors") (part "Resistor - 1%"))
    )
    (comp (ref "R68")
      (value "49R9")
      (footprint "RESC1005X40N")
      (description "Resistor - 1%")
      (fields
        (field (name "PART NUMBER") "R0402_49R9_1%_0.0625W_100PPM")
        (field (name "POWER") "0.0625W")
        (field (name "AUTHOR") "CERN DEM JLC")
      )
      (libsource (lib "Resistors") (part "Resistor - 1%"))
    )
    (comp (ref "R69")
      (value "95R3")
      (footprint "RESC1608X55N")
      (description "Resistor - 0.1%")
      (fields
        (field (name "PART NUMBER") "R0603_95R3_0.1%_0.063W_10PPM")
        (field (name "POWER") "0.063W")
        (field (name "AUTHOR") "CERN DEM JLC")
      )
      (libsource (lib "Resistors") (part "Resistor - 0.1%"))
    )
    (comp (ref "R70")
      (value "82R5")
      (footprint "RESC1608X55N")
      (description "Resistor - 0.1%")
      (fields
        (field (name "PART NUMBER") "R0603_82R5_0.1%_0.063W_10PPM")
        (field (name "POWER") "0.063W")
        (field (name "AUTHOR") "CERN DEM JLC")
      )
      (libsource (lib "Resistors") (part "Resistor - 0.1%"))
    )
    (comp (ref "R71")
      (value "82R5")
      (footprint "RESC1608X55N")
      (description "Resistor - 0.1%")
      (fields
        (field (name "PART NUMBER") "R0603_82R5_0.1%_0.063W_10PPM")
        (field (name "POWER") "0.063W")
        (field (name "AUTHOR") "CERN DEM JLC")
      )
      (libsource (lib "Resistors") (part "Resistor - 0.1%"))
    )
    (comp (ref "R72")
      (value "49R9")
      (footprint "RESC1005X40N")
      (description "Resistor - 1%")
      (fields
        (field (name "PART NUMBER") "R0402_49R9_1%_0.0625W_100PPM")
        (field (name "POWER") "0.0625W")
        (field (name "AUTHOR") "CERN DEM JLC")
      )
      (libsource (lib "Resistors") (part "Resistor - 1%"))
    )
    (comp (ref "R73")
      (value "1k")
      (footprint "RESC1005X40N")
      (description "Resistor - 1%")
      (fields
        (field (name "PART NUMBER") "R0402_1K_1%_0.0625W_100PPM")
        (field (name "POWER") "0.0625W")
        (field (name "AUTHOR") "CERN DEM JLC")
      )
      (libsource (lib "Resistors") (part "Resistor - 1%"))
    )
    (comp (ref "R74")
      (value "0")
      (footprint "RESC1005X40N")
      (description "Resistor")
      (fields
        (field (name "PART NUMBER") "R0402_0R_JUMPER")
        (field (name "MANUFACTURER") "GENERIC")
        (field (name "AUTHOR") "CERN DEM JLC")
      )
      (libsource (lib "Resistors") (part "Resistor"))
    )
    (comp (ref "R75")
      (value "0")
      (footprint "RESC1005X40N")
      (description "Resistor")
      (fields
        (field (name "PART NUMBER") "R0402_0R_JUMPER")
        (field (name "MANUFACTURER") "GENERIC")
        (field (name "AUTHOR") "CERN DEM JLC")
      )
      (libsource (lib "Resistors") (part "Resistor"))
    )
    (comp (ref "R76")
      (value "220k")
      (footprint "RESC1005X40N")
      (description "Resistor - 1%")
      (fields
        (field (name "PART NUMBER") "R0402_220K_1%_0.0625W_100PPM")
        (field (name "POWER") "0.0625W")
        (field (name "AUTHOR") "CERN DEM JLC")
      )
      (libsource (lib "Resistors") (part "Resistor - 1%"))
    )
    (comp (ref "R77")
      (value "100")
      (footprint "RESC1005X40N")
      (description "Resistor - 1%")
      (fields
        (field (name "PART NUMBER") "R0402_100R_1%_0.0625W_100PPM")
        (field (name "POWER") "0.0625W")
        (field (name "AUTHOR") "CERN DEM JLC")
      )
      (libsource (lib "Resistors") (part "Resistor - 1%"))
    )
    (comp (ref "R78")
      (value "17R8")
      (footprint "RESC1608X55N")
      (description "Resistor - 0.1%")
      (fields
        (field (name "PART NUMBER") "R0603_17R8_0.1%_0.063W_10PPM")
        (field (name "POWER") "0.063W")
        (field (name "AUTHOR") "CERN DEM JLC")
      )
      (libsource (lib "Resistors") (part "Resistor - 0.1%"))
    )
    (comp (ref "R79")
      (value "49R9")
      (footprint "RESC1005X40N")
      (description "Resistor - 1%")
      (fields
        (field (name "PART NUMBER") "R0402_49R9_1%_0.0625W_100PPM")
        (field (name "POWER") "0.0625W")
        (field (name "AUTHOR") "CERN DEM JLC")
      )
      (libsource (lib "Resistors") (part "Resistor - 1%"))
    )
    (comp (ref "R80")
      (value "270")
      (footprint "RESC1005X40N")
      (description "Resistor - 1%")
      (fields
        (field (name "PART NUMBER") "R0402_270R_1%_0.0625W_100PPM")
        (field (name "POWER") "0.0625W")
        (field (name "AUTHOR") "CERN DEM JLC")
      )
      (libsource (lib "Resistors") (part "Resistor - 1%"))
    )
    (comp (ref "R81")
      (value "270")
      (footprint "RESC1005X40N")
      (description "Resistor - 1%")
      (fields
        (field (name "PART NUMBER") "R0402_270R_1%_0.0625W_100PPM")
        (field (name "POWER") "0.0625W")
        (field (name "AUTHOR") "CERN DEM JLC")
      )
      (libsource (lib "Resistors") (part "Resistor - 1%"))
    )
    (comp (ref "R82")
      (value "Undefined")
      (footprint "RESC1005X40N")
      (description "Resistor")
      (fields (field (name "PART NUMBER") "R0402_NO-VALUE") (field (name "AUTHOR") "CERN DEM JLC"))
      (libsource (lib "Resistors") (part "Resistor"))
    )
    (comp (ref "R83")
      (value "43")
      (footprint "RESC1005X40N")
      (description "Resistor - 1%")
      (fields
        (field (name "PART NUMBER") "R0402_43R_1%_0.0625W_100PPM")
        (field (name "POWER") "0.0625W")
        (field (name "AUTHOR") "CERN DEM JLC")
      )
      (libsource (lib "Resistors") (part "Resistor - 1%"))
    )
    (comp (ref "R84")
      (value "43")
      (footprint "RESC1005X40N")
      (description "Resistor - 1%")
      (fields
        (field (name "PART NUMBER") "R0402_43R_1%_0.0625W_100PPM")
        (field (name "POWER") "0.0625W")
        (field (name "AUTHOR") "CERN DEM JLC")
      )
      (libsource (lib "Resistors") (part "Resistor - 1%"))
    )
    (comp (ref "R85")
      (value "43")
      (footprint "RESC1005X40N")
      (description "Resistor - 1%")
      (fields
        (field (name "PART NUMBER") "R0402_43R_1%_0.0625W_100PPM")
        (field (name "POWER") "0.0625W")
        (field (name "AUTHOR") "CERN DEM JLC")
      )
      (libsource (lib "Resistors") (part "Resistor - 1%"))
    )
    (comp (ref "R86")
      (value "100")
      (footprint "RESC1005X40N")
      (description "Resistor - 1%")
      (fields
        (field (name "PART NUMBER") "R0402_100R_1%_0.0625W_100PPM")
        (field (name "POWER") "0.0625W")
        (field (name "AUTHOR") "CERN DEM JLC")
      )
      (libsource (lib "Resistors") (part "Resistor - 1%"))
    )
    (comp (ref "R87")
      (value "330")
      (footprint "RESC1005X40N")
      (description "Resistor - 1%")
      (fields
        (field (name "TOLERANCE") "±1%")
        (field (name "POWER") "0.0625W")
        (field (name "AUTHOR") "CERN DEM JLC")
      )
      (libsource (lib "Resistors") (part "Resistor - 1%"))
    )
  )
  (nets
    (net (code "4") (name "/CLK") (class "Default")
      (node (ref "R59") (pin "2") (pinfunction "2_2") (pintype "passive"))
    )
    (net (code "5") (name "/CLK_4208_IN0_CMOS") (class "Default")
      (node (ref "C165") (pin "2") (pinfunction "2_2") (pintype "passive"))
      (node (ref "IC8") (pin "28") (pinfunction "CLKIN0_28") (pintype "input"))
    )
    (net (code "6") (name "/CLK_4208_IN0_M") (class "Default")
      (node (ref "C127") (pin "2") (pinfunction "2_2") (pintype "passive"))
      (node (ref "IC8") (pin "29") (pinfunction "~{CLKIN0}_29") (pintype "input"))
    )
    (net (code "7") (name "/CLK_4208_IN1_C_N") (class "Default")
      (node (ref "C138") (pin "2") (pinfunction "2_2") (pintype "passive"))
      (node (ref "IC8") (pin "26") (pinfunction "~{FBCLKIN}/~{FIN}/~{CLKIN1}_26") (pintype "input"))
    )
    (net (code "8") (name "/CLK_4208_IN1_C_P") (class "Default")
      (node (ref "C137") (pin "2") (pinfunction "2_2") (pintype "passive"))
      (node (ref "IC8") (pin "25") (pinfunction "FBCLKIN/FIN/CLKIN1_25") (pintype "input"))
    )
    (net (code "9") (name "/CLK_4208_IN1_N") (class "Default")
      (node (ref "C138") (pin "1") (pinfunction "1_1") (pintype "passive"))
      (node (ref "R64") (pin "1") (pinfunction "1_1") (pintype "passive"))
    )
    (net (code "10") (name "/CLK_4208_IN1_P") (class "Default")
      (node (ref "C137") (pin "1") (pinfunction "1_1") (pintype "passive"))
      (node (ref "R64") (pin "2") (pinfunction "2_2") (pintype "passive"))
    )
    (net (code "11") (name "/CLK_4208_OUT0_N") (class "Default")
      (node (ref "C107") (pin "1") (pinfunction "1_1") (pintype "passive"))
      (node (ref "IC8") (pin "3") (pinfunction "~{CLKOUT0}_3") (pintype "output"))
      (node (ref "R55") (pin "2") (pinfunction "2_2") (pintype "passive"))
    )
    (net (code "12") (name "/CLK_4208_OUT0_P") (class "Default")
      (node (ref "C94") (pin "1") (pinfunction "1_1") (pintype "passive"))
      (node (ref "IC8") (pin "4") (pinfunction "CLKOUT_4") (pintype "output"))
      (node (ref "R54") (pin "2") (pinfunction "2_2") (pintype "passive"))
    )
    (net (code "13") (name "/CLK_4208_OUT1_N") (class "Default")
      (node (ref "C114") (pin "1") (pinfunction "1_1") (pintype "passive"))
      (node (ref "IC8") (pin "14") (pinfunction "~{CLKOUT1}_14") (pintype "output"))
      (node (ref "R57") (pin "2") (pinfunction "2_2") (pintype "passive"))
    )
    (net (code "14") (name "/CLK_4208_OUT1_P") (class "Default")
      (node (ref "C113") (pin "1") (pinfunction "1_1") (pintype "passive"))
      (node (ref "IC8") (pin "13") (pinfunction "CLKOUT1_13") (pintype "output"))
      (node (ref "R56") (pin "2") (pinfunction "2_2") (pintype "passive"))
    )
    (net (code "15") (name "/CLK_4208_OUT2_N") (class "Default")
      (node (ref "C126") (pin "1") (pinfunction "1_1") (pintype "passive"))
      (node (ref "IC8") (pin "21") (pinfunction "~{CLKOUT2}_21") (pintype "output"))
      (node (ref "R63") (pin "2") (pinfunction "2_2") (pintype "passive"))
    )
    (net (code "16") (name "/CLK_4208_OUT2_P") (class "Default")
      (node (ref "C125") (pin "1") (pinfunction "1_1") (pintype "passive"))
      (node (ref "IC8") (pin "22") (pinfunction "CLKOUT2_22") (pintype "output"))
      (node (ref "R62") (pin "2") (pinfunction "2_2") (pintype "passive"))
    )
    (net (code "17") (name "/CLK_4208_OUT3_N") (class "Default")
      (node (ref "IC10") (pin "6") (pinfunction "nCLK_6") (pintype "input"))
      (node (ref "IC8") (pin "49") (pinfunction "~{CLKOUT3}_49") (pintype "output"))
      (node (ref "R86") (pin "1") (pinfunction "1_1") (pintype "passive"))
    )
    (net (code "18") (name "/CLK_4208_OUT3_P") (class "Default")
      (node (ref "IC10") (pin "5") (pinfunction "CLK_5") (pintype "input"))
      (node (ref "IC8") (pin "48") (pinfunction "CLKOUT3_48") (pintype "output"))
      (node (ref "R86") (pin "2") (pinfunction "2_2") (pintype "passive"))
    )
    (net (code "19") (name "/CLK_4208_OUT4_N") (class "Default")
      (node (ref "IC8") (pin "54") (pinfunction "~{CLKOUT4}_54") (pintype "output"))
      (node (ref "IC9") (pin "15") (pinfunction "~{CLKIN0}_15") (pintype "input"))
      (node (ref "R77") (pin "1") (pinfunction "1_1") (pintype "passive"))
    )
    (net (code "20") (name "/CLK_4208_OUT4_P") (class "Default")
      (node (ref "IC8") (pin "53") (pinfunction "CLKOUT4_53") (pintype "output"))
      (node (ref "IC9") (pin "14") (pinfunction "CLKIN0_14") (pintype "input"))
      (node (ref "R77") (pin "2") (pinfunction "2_2") (pintype "passive"))
    )
    (net (code "21") (name "/CLK_4208_OUT5") (class "Default")
      (node (ref "IC8") (pin "58") (pinfunction "CLKOUT5_58") (pintype "output"))
      (node (ref "R61") (pin "1") (pinfunction "1_1") (pintype "passive"))
    )
    (net (code "22") (name "/CLK_4208_OUT5_ATT") (class "Default")
      (node (ref "C131") (pin "1") (pinfunction "1_1") (pintype "passive"))
      (node (ref "R61") (pin "2") (pinfunction "2_2") (pintype "passive"))
      (node (ref "R66") (pin "2") (pinfunction "2_2") (pintype "passive"))
    )
    (net (code "23") (name "/CLK_4208_OUT5_C") (class "Default")
      (node (ref "C131") (pin "2") (pinfunction "2_2") (pintype "passive"))
      (node (ref "J25") (pin "1") (pinfunction "1_1") (pintype "bidirectional"))
      (node (ref "R65") (pin "2") (pinfunction "2_2") (pintype "passive"))
    )
    (net (code "24") (name "/CLK_4208_OUT5_M") (class "Default")
      (node (ref "C139") (pin "1") (pinfunction "1_1") (pintype "passive"))
      (node (ref "IC8") (pin "59") (pinfunction "~{CLKOUT5}_59") (pintype "output"))
      (node (ref "R67") (pin "2") (pinfunction "2_2") (pintype "passive"))
    )
    (net (code "25") (name "/CLK_IN1") (class "Default")
      (node (ref "C164") (pin "1") (pinfunction "1_1") (pintype "passive"))
      (node (ref "J2") (pin "1") (pinfunction "1_1") (pintype "bidirectional"))
      (node (ref "R79") (pin "2") (pinfunction "2_2") (pintype "passive"))
    )
    (net (code "26") (name "/CLK_IN1_AC") (class "Default")
      (node (ref "C164") (pin "2") (pinfunction "2_2") (pintype "passive"))
      (node (ref "R78") (pin "1") (pinfunction "1_1") (pintype "passive"))
      (node (ref "R80") (pin "2") (pinfunction "2_2") (pintype "passive"))
    )
    (net (code "27") (name "/CLK_IN1_ATT") (class "Default")
      (node (ref "C165") (pin "1") (pinfunction "1_1") (pintype "passive"))
      (node (ref "R78") (pin "2") (pinfunction "2_2") (pintype "passive"))
      (node (ref "R81") (pin "2") (pinfunction "2_2") (pintype "passive"))
      (node (ref "R82") (pin "2") (pinfunction "2_2") (pintype "passive"))
    )
    (net (code "28") (name "/DATA") (class "Default")
      (node (ref "R60") (pin "2") (pinfunction "2_2") (pintype "passive"))
    )
    (net (code "29") (name "/FPGA_REFCLK_OUT_C_N") (class "Default")
      (node (ref "C126") (pin "2") (pinfunction "2_2") (pintype "passive"))
    )
    (net (code "30") (name "/FPGA_REFCLK_OUT_C_P") (class "Default")
      (node (ref "C125") (pin "2") (pinfunction "2_2") (pintype "passive"))
    )
    (net (code "31") (name "/LE") (class "Default")
      (node (ref "R58") (pin "2") (pinfunction "2_2") (pintype "passive"))
    )
    (net (code "32") (name "/LMK04208_CPO1") (class "Default")
      (node (ref "IC8") (pin "34") (pinfunction "CPOUT1_34") (pintype "output"))
      (node (ref "R75") (pin "2") (pinfunction "2_2") (pintype "passive"))
    )
    (net (code "33") (name "/LMK04208_CPO2") (class "Default")
      (node (ref "C147") (pin "2") (pinfunction "2_2") (pintype "passive"))
      (node (ref "C148") (pin "2") (pinfunction "2_2") (pintype "passive"))
      (node (ref "IC8") (pin "42") (pinfunction "CPOUT2_42") (pintype "output"))
    )
    (net (code "34") (name "/LMX2594A") (class "Default")
      (node (ref "R83") (pin "2") (pinfunction "2_2") (pintype "passive"))
    )
    (net (code "35") (name "/LMX2594B") (class "Default")
      (node (ref "R84") (pin "2") (pinfunction "2_2") (pintype "passive"))
    )
    (net (code "36") (name "/LMX2594C") (class "Default")
      (node (ref "R85") (pin "2") (pinfunction "2_2") (pintype "passive"))
    )
    (net (code "37") (name "/MUXOUT") (class "Default")
      (node (ref "IC8") (pin "27") (pinfunction "STATUS_HOLDOVER_27") (pintype "bidirectional"))
    )
    (net (code "38") (name "/OSCIN_4208_CMOS") (class "Default")
      (node (ref "C141") (pin "2") (pinfunction "2_2") (pintype "passive"))
      (node (ref "IC8") (pin "36") (pinfunction "OSCIN_36") (pintype "input"))
    )
    (net (code "39") (name "/OSCIN_4208_M") (class "Default")
      (node (ref "C140") (pin "2") (pinfunction "2_2") (pintype "passive"))
      (node (ref "IC8") (pin "37") (pinfunction "~{OSCIN}_37") (pintype "input"))
    )
    (net (code "40") (name "/REFIN_2594A_N") (class "Default")
      (node (ref "IC9") (pin "18") (pinfunction "~{CLKOUTB}1_18") (pintype "output"))
    )
    (net (code "41") (name "/REFIN_2594A_P") (class "Default")
      (node (ref "IC9") (pin "19") (pinfunction "CLKOUTB1_19") (pintype "output"))
    )
    (net (code "42") (name "/REFIN_2594B_N") (class "Default")
      (node (ref "IC9") (pin "21") (pinfunction "~{CLKOUTB0}_21") (pintype "output"))
    )
    (net (code "43") (name "/REFIN_2594B_P") (class "Default")
      (node (ref "IC9") (pin "22") (pinfunction "CLKOUTB0_22") (pintype "output"))
    )
    (net (code "44") (name "/REFIN_2594C_N") (class "Default")
      (node (ref "IC9") (pin "7") (pinfunction "~{CLKOUTA1}_7") (pintype "output"))
    )
    (net (code "45") (name "/REFIN_2594C_P") (class "Default")
      (node (ref "IC9") (pin "6") (pinfunction "CLKOUTA1_6") (pintype "output"))
    )
    (net (code "46") (name "/STATUS_4208") (class "Default")
      (node (ref "DS1") (pin "2") (pinfunction "A_2") (pintype "passive"))
      (node (ref "IC8") (pin "33") (pinfunction "STATUS_LD_33") (pintype "bidirectional"))
    )
    (net (code "47") (name "/SYSREF_FPGA_C_N") (class "Default")
      (node (ref "C107") (pin "2") (pinfunction "2_2") (pintype "passive"))
    )
    (net (code "48") (name "/SYSREF_FPGA_C_P") (class "Default")
      (node (ref "C94") (pin "2") (pinfunction "2_2") (pintype "passive"))
    )
    (net (code "49") (name "/SYSREF_RFSOC_C_N") (class "Default")
      (node (ref "C114") (pin "2") (pinfunction "2_2") (pintype "passive"))
    )
    (net (code "50") (name "/SYSREF_RFSOC_C_P") (class "Default")
      (node (ref "C113") (pin "2") (pinfunction "2_2") (pintype "passive"))
    )
    (net (code "51") (name "/VCC_4208_CKO_0") (class "Default")
      (node (ref "C129") (pin "2") (pinfunction "2_2") (pintype "passive"))
      (node (ref "C130") (pin "2") (pinfunction "2_2") (pintype "passive"))
      (node (ref "IC8") (pin "64") (pinfunction "VCC13_64") (pintype "power_in"))
      (node (ref "L14") (pin "2") (pinfunction "2_2") (pintype "passive"))
    )
    (net (code "52") (name "/VCC_4208_CKO_1") (class "Default")
      (node (ref "C143") (pin "2") (pinfunction "2_2") (pintype "passive"))
      (node (ref "C144") (pin "2") (pinfunction "2_2") (pintype "passive"))
      (node (ref "IC8") (pin "17") (pinfunction "VCC2_17") (pintype "power_in"))
      (node (ref "L15") (pin "2") (pinfunction "2_2") (pintype "passive"))
    )
    (net (code "53") (name "/VCC_4208_CKO_2") (class "Default")
      (node (ref "C150") (pin "2") (pinfunction "2_2") (pintype "passive"))
      (node (ref "C151") (pin "2") (pinfunction "2_2") (pintype "passive"))
      (node (ref "IC8") (pin "18") (pinfunction "VCC3_18") (pintype "power_in"))
      (node (ref "L16") (pin "2") (pinfunction "2_2") (pintype "passive"))
    )
    (net (code "54") (name "/VCC_4208_CKO_3") (class "Default")
      (node (ref "C153") (pin "2") (pinfunction "2_2") (pintype "passive"))
      (node (ref "C154") (pin "2") (pinfunction "2_2") (pintype "passive"))
      (node (ref "IC8") (pin "47") (pinfunction "VCC10_47") (pintype "power_in"))
      (node (ref "L17") (pin "2") (pinfunction "2_2") (pintype "passive"))
    )
    (net (code "55") (name "/VCC_4208_CKO_4") (class "Default")
      (node (ref "C159") (pin "2") (pinfunction "2_2") (pintype "passive"))
      (node (ref "C160") (pin "2") (pinfunction "2_2") (pintype "passive"))
      (node (ref "IC8") (pin "52") (pinfunction "VCC11_52") (pintype "power_in"))
      (node (ref "L18") (pin "2") (pinfunction "2_2") (pintype "passive"))
    )
    (net (code "56") (name "/VCC_4208_CKO_5") (class "Default")
      (node (ref "C162") (pin "2") (pinfunction "2_2") (pintype "passive"))
      (node (ref "C163") (pin "2") (pinfunction "2_2") (pintype "passive"))
      (node (ref "IC8") (pin "57") (pinfunction "VCC12_57") (pintype "power_in"))
      (node (ref "L19") (pin "2") (pinfunction "2_2") (pintype "passive"))
    )
    (net (code "57") (name "/VCC_4208_CLKO") (class "Default")
      (node (ref "C133") (pin "2") (pinfunction "2_2") (pintype "passive"))
      (node (ref "C134") (pin "2") (pinfunction "2_2") (pintype "passive"))
      (node (ref "C135") (pin "2") (pinfunction "2_2") (pintype "passive"))
      (node (ref "C136") (pin "2") (pinfunction "2_2") (pintype "passive"))
      (node (ref "C142") (pin "2") (pinfunction "2_2") (pintype "passive"))
      (node (ref "C149") (pin "2") (pinfunction "2_2") (pintype "passive"))
      (node (ref "C152") (pin "2") (pinfunction "2_2") (pintype "passive"))
      (node (ref "C158") (pin "2") (pinfunction "2_2") (pintype "passive"))
      (node (ref "C161") (pin "2") (pinfunction "2_2") (pintype "passive"))
      (node (ref "L13") (pin "2") (pinfunction "2_2") (pintype "passive"))
      (node (ref "L14") (pin "1") (pinfunction "1_1") (pintype "passive"))
      (node (ref "L15") (pin "1") (pinfunction "1_1") (pintype "passive"))
      (node (ref "L16") (pin "1") (pinfunction "1_1") (pintype "passive"))
      (node (ref "L17") (pin "1") (pinfunction "1_1") (pintype "passive"))
      (node (ref "L18") (pin "1") (pinfunction "1_1") (pintype "passive"))
      (node (ref "L19") (pin "1") (pinfunction "1_1") (pintype "passive"))
    )
    (net (code "58") (name "/VCC_4208_PLL") (class "Default")
      (node (ref "C100") (pin "2") (pinfunction "2_2") (pintype "passive"))
      (node (ref "C101") (pin "2") (pinfunction "2_2") (pintype "passive"))
      (node (ref "C102") (pin "2") (pinfunction "2_2") (pintype "passive"))
      (node (ref "C103") (pin "2") (pinfunction "2_2") (pintype "passive"))
      (node (ref "C104") (pin "2") (pinfunction "2_2") (pintype "passive"))
      (node (ref "C105") (pin "2") (pinfunction "2_2") (pintype "passive"))
      (node (ref "C106") (pin "2") (pinfunction "2_2") (pintype "passive"))
      (node (ref "C109") (pin "2") (pinfunction "2_2") (pintype "passive"))
      (node (ref "C110") (pin "2") (pinfunction "2_2") (pintype "passive"))
      (node (ref "C115") (pin "2") (pinfunction "2_2") (pintype "passive"))
      (node (ref "C116") (pin "2") (pinfunction "2_2") (pintype "passive"))
      (node (ref "C96") (pin "2") (pinfunction "2_2") (pintype "passive"))
      (node (ref "C97") (pin "1") (pinfunction "1_1") (pintype "passive"))
      (node (ref "C98") (pin "2") (pinfunction "2_2") (pintype "passive"))
      (node (ref "C99") (pin "2") (pinfunction "2_2") (pintype "passive"))
      (node (ref "IC8") (pin "10") (pinfunction "VCC1_10") (pintype "power_in"))
      (node (ref "IC8") (pin "24") (pinfunction "VCC4_24") (pintype "power_in"))
      (node (ref "IC8") (pin "30") (pinfunction "VCC5_30") (pintype "power_in"))
      (node (ref "IC8") (pin "38") (pinfunction "VCC7_38") (pintype "power_in"))
      (node (ref "IC8") (pin "43") (pinfunction "VCC9_43") (pintype "power_in"))
      (node (ref "L10") (pin "1") (pinfunction "1_1") (pintype "passive"))
      (node (ref "L11") (pin "1") (pinfunction "1_1") (pintype "passive"))
      (node (ref "L9") (pin "2") (pinfunction "2_2") (pintype "passive"))
    )
    (net (code "59") (name "/VCC_4208_PLL1_CP") (class "Default")
      (node (ref "C111") (pin "2") (pinfunction "2_2") (pintype "passive"))
      (node (ref "C112") (pin "2") (pinfunction "2_2") (pintype "passive"))
      (node (ref "IC8") (pin "35") (pinfunction "VCC6_35") (pintype "power_in"))
      (node (ref "L10") (pin "2") (pinfunction "2_2") (pintype "passive"))
    )
    (net (code "60") (name "/VCC_4208_PLL2_CP") (class "Default")
      (node (ref "C117") (pin "2") (pinfunction "2_2") (pintype "passive"))
      (node (ref "C118") (pin "2") (pinfunction "2_2") (pintype "passive"))
      (node (ref "IC8") (pin "41") (pinfunction "VCC8_41") (pintype "power_in"))
      (node (ref "L11") (pin "2") (pinfunction "2_2") (pintype "passive"))
    )
    (net (code "61") (name "/VCC_VCXO") (class "Default")
      (node (ref "C121") (pin "2") (pinfunction "2_2") (pintype "passive"))
      (node (ref "C122") (pin "2") (pinfunction "2_2") (pintype "passive"))
      (node (ref "C123") (pin "2") (pinfunction "2_2") (pintype "passive"))
      (node (ref "C124") (pin "2") (pinfunction "2_2") (pintype "passive"))
      (node (ref "L12") (pin "2") (pinfunction "2_2") (pintype "passive"))
      (node (ref "OSC1") (pin "4") (pinfunction "VDD_4") (pintype "power_in"))
    )
    (net (code "62") (name "/VCXO_OUT") (class "Default")
      (node (ref "OSC1") (pin "3") (pinfunction "OUT_3") (pintype "output"))
      (node (ref "R69") (pin "1") (pinfunction "1_1") (pintype "passive"))
      (node (ref "R70") (pin "2") (pinfunction "2_2") (pintype "passive"))
    )
    (net (code "63") (name "/VCXO_OUT_ATT") (class "Default")
      (node (ref "C141") (pin "1") (pinfunction "1_1") (pintype "passive"))
      (node (ref "R69") (pin "2") (pinfunction "2_2") (pintype "passive"))
      (node (ref "R71") (pin "2") (pinfunction "2_2") (pintype "passive"))
      (node (ref "R72") (pin "2") (pinfunction "2_2") (pintype "passive"))
    )
    (net (code "64") (name "/VTUEN_VCO1") (class "Default")
      (node (ref "C155") (pin "2") (pinfunction "2_2") (pintype "passive"))
      (node (ref "OSC1") (pin "1") (pinfunction "VC_1") (pintype "input"))
      (node (ref "R74") (pin "1") (pinfunction "1_1") (pintype "passive"))
    )
    (net (code "68") (name "AMS_CLK_VCC3V3") (class "Default")
      (node (ref "C120") (pin "2") (pinfunction "2_2") (pintype "passive"))
      (node (ref "C128") (pin "2") (pinfunction "2_2") (pintype "passive"))
      (node (ref "C132") (pin "2") (pinfunction "2_2") (pintype "passive"))
      (node (ref "C169") (pin "2") (pinfunction "2_2") (pintype "passive"))
      (node (ref "C170") (pin "2") (pinfunction "2_2") (pintype "passive"))
      (node (ref "C174") (pin "2") (pinfunction "2_2") (pintype "passive"))
      (node (ref "C175") (pin "2") (pinfunction "2_2") (pintype "passive"))
      (node (ref "C95") (pin "2") (pinfunction "2_2") (pintype "passive"))
      (node (ref "L12") (pin "1") (pinfunction "1_1") (pintype "passive"))
      (node (ref "L13") (pin "1") (pinfunction "1_1") (pintype "passive"))
      (node (ref "L20") (pin "1") (pinfunction "1_1") (pintype "passive"))
      (node (ref "L21") (pin "1") (pinfunction "1_1") (pintype "passive"))
      (node (ref "L9") (pin "1") (pinfunction "1_1") (pintype "passive"))
    )
    (net (code "69") (name "GND") (class "Default")
      (node (ref "C100") (pin "1") (pinfunction "1_1") (pintype "passive"))
      (node (ref "C101") (pin "1") (pinfunction "1_1") (pintype "passive"))
      (node (ref "C102") (pin "1") (pinfunction "1_1") (pintype "passive"))
      (node (ref "C103") (pin "1") (pinfunction "1_1") (pintype "passive"))
      (node (ref "C104") (pin "1") (pinfunction "1_1") (pintype "passive"))
      (node (ref "C105") (pin "1") (pinfunction "1_1") (pintype "passive"))
      (node (ref "C106") (pin "1") (pinfunction "1_1") (pintype "passive"))
      (node (ref "C109") (pin "1") (pinfunction "1_1") (pintype "passive"))
      (node (ref "C110") (pin "1") (pinfunction "1_1") (pintype "passive"))
      (node (ref "C111") (pin "1") (pinfunction "1_1") (pintype "passive"))
      (node (ref "C112") (pin "1") (pinfunction "1_1") (pintype "passive"))
      (node (ref "C115") (pin "1") (pinfunction "1_1") (pintype "passive"))
      (node (ref "C116") (pin "1") (pinfunction "1_1") (pintype "passive"))
      (node (ref "C117") (pin "1") (pinfunction "1_1") (pintype "passive"))
      (node (ref "C118") (pin "1") (pinfunction "1_1") (pintype "passive"))
      (node (ref "C120") (pin "1") (pinfunction "1_1") (pintype "passive"))
      (node (ref "C121") (pin "1") (pinfunction "1_1") (pintype "passive"))
      (node (ref "C122") (pin "1") (pinfunction "1_1") (pintype "passive"))
      (node (ref "C123") (pin "1") (pinfunction "1_1") (pintype "passive"))
      (node (ref "C124") (pin "1") (pinfunction "1_1") (pintype "passive"))
      (node (ref "C127") (pin "1") (pinfunction "1_1") (pintype "passive"))
      (node (ref "C128") (pin "1") (pinfunction "1_1") (pintype "passive"))
      (node (ref "C129") (pin "1") (pinfunction "1_1") (pintype "passive"))
      (node (ref "C130") (pin "1") (pinfunction "1_1") (pintype "passive"))
      (node (ref "C132") (pin "1") (pinfunction "1_1") (pintype "passive"))
      (node (ref "C133") (pin "1") (pinfunction "1_1") (pintype "passive"))
      (node (ref "C134") (pin "1") (pinfunction "1_1") (pintype "passive"))
      (node (ref "C135") (pin "1") (pinfunction "1_1") (pintype "passive"))
      (node (ref "C136") (pin "1") (pinfunction "1_1") (pintype "passive"))
      (node (ref "C140") (pin "1") (pinfunction "1_1") (pintype "passive"))
      (node (ref "C142") (pin "1") (pinfunction "1_1") (pintype "passive"))
      (node (ref "C143") (pin "1") (pinfunction "1_1") (pintype "passive"))
      (node (ref "C144") (pin "1") (pinfunction "1_1") (pintype "passive"))
      (node (ref "C145") (pin "1") (pinfunction "1_1") (pintype "passive"))
      (node (ref "C146") (pin "1") (pinfunction "1_1") (pintype "passive"))
      (node (ref "C147") (pin "1") (pinfunction "1_1") (pintype "passive"))
      (node (ref "C149") (pin "1") (pinfunction "1_1") (pintype "passive"))
      (node (ref "C150") (pin "1") (pinfunction "1_1") (pintype "passive"))
      (node (ref "C151") (pin "1") (pinfunction "1_1") (pintype "passive"))
      (node (ref "C152") (pin "1") (pinfunction "1_1") (pintype "passive"))
      (node (ref "C153") (pin "1") (pinfunction "1_1") (pintype "passive"))
      (node (ref "C154") (pin "1") (pinfunction "1_1") (pintype "passive"))
      (node (ref "C155") (pin "1") (pinfunction "1_1") (pintype "passive"))
      (node (ref "C157") (pin "1") (pinfunction "1_1") (pintype "passive"))
      (node (ref "C158") (pin "1") (pinfunction "1_1") (pintype "passive"))
      (node (ref "C159") (pin "1") (pinfunction "1_1") (pintype "passive"))
      (node (ref "C160") (pin "1") (pinfunction "1_1") (pintype "passive"))
      (node (ref "C161") (pin "1") (pinfunction "1_1") (pintype "passive"))
      (node (ref "C162") (pin "1") (pinfunction "1_1") (pintype "passive"))
      (node (ref "C163") (pin "1") (pinfunction "1_1") (pintype "passive"))
      (node (ref "C166") (pin "1") (pinfunction "1_1") (pintype "passive"))
      (node (ref "C167") (pin "1") (pinfunction "1_1") (pintype "passive"))
      (node (ref "C168") (pin "1") (pinfunction "1_1") (pintype "passive"))
      (node (ref "C169") (pin "1") (pinfunction "1_1") (pintype "passive"))
      (node (ref "C170") (pin "1") (pinfunction "1_1") (pintype "passive"))
      (node (ref "C171") (pin "1") (pinfunction "1_1") (pintype "passive"))
      (node (ref "C172") (pin "1") (pinfunction "1_1") (pintype "passive"))
      (node (ref "C173") (pin "1") (pinfunction "1_1") (pintype "passive"))
      (node (ref "C174") (pin "1") (pinfunction "1_1") (pintype "passive"))
      (node (ref "C175") (pin "1") (pinfunction "1_1") (pintype "passive"))
      (node (ref "C553") (pin "1") (pinfunction "1_1") (pintype "passive"))
      (node (ref "C554") (pin "1") (pinfunction "1_1") (pintype "passive"))
      (node (ref "C557") (pin "1") (pinfunction "1_1") (pintype "passive"))
      (node (ref "C558") (pin "1") (pinfunction "1_1") (pintype "passive"))
      (node (ref "C95") (pin "1") (pinfunction "1_1") (pintype "passive"))
      (node (ref "C96") (pin "1") (pinfunction "1_1") (pintype "passive"))
      (node (ref "C97") (pin "2") (pinfunction "2_2") (pintype "passive"))
      (node (ref "C98") (pin "1") (pinfunction "1_1") (pintype "passive"))
      (node (ref "C99") (pin "1") (pinfunction "1_1") (pintype "passive"))
      (node (ref "IC10") (pin "1") (pinfunction "GND_1") (pintype "power_in"))
      (node (ref "IC10") (pin "13") (pinfunction "GND_13") (pintype "power_in"))
      (node (ref "IC10") (pin "9") (pinfunction "GND_9") (pintype "power_in"))
      (node (ref "IC8") (pin "23") (pinfunction "GND_23") (pintype "power_in"))
      (node (ref "IC8") (pin "65") (pinfunction "GND_65") (pintype "power_in"))
      (node (ref "IC9") (pin "1") (pinfunction "GND_1") (pintype "power_in"))
      (node (ref "IC9") (pin "13") (pinfunction "CLKIN_SEL0_13") (pintype "input"))
      (node (ref "IC9") (pin "16") (pinfunction "CLKIN_SEL_16") (pintype "input"))
      (node (ref "IC9") (pin "17") (pinfunction "GND_17") (pintype "power_in"))
      (node (ref "IC9") (pin "24") (pinfunction "GND_24") (pintype "power_in"))
      (node (ref "IC9") (pin "32") (pinfunction "CLKOUT_TYPE1_32") (pintype "input"))
      (node (ref "IC9") (pin "33") (pinfunction "GND_33") (pintype "power_in"))
      (node (ref "IC9") (pin "8") (pinfunction "GND_8") (pintype "power_in"))
      (node (ref "J2") (pin "2") (pinfunction "2_2") (pintype "bidirectional"))
      (node (ref "J25") (pin "2") (pinfunction "2_2") (pintype "bidirectional"))
      (node (ref "MSBOX5") (pin "1") (pinfunction "1_1") (pintype "passive"))
      (node (ref "MSBOX5") (pin "10") (pinfunction "10_10") (pintype "passive"))
      (node (ref "MSBOX5") (pin "11") (pinfunction "11_11") (pintype "passive"))
      (node (ref "MSBOX5") (pin "12") (pinfunction "12_12") (pintype "passive"))
      (node (ref "MSBOX5") (pin "13") (pinfunction "13_13") (pintype "passive"))
      (node (ref "MSBOX5") (pin "14") (pinfunction "14_14") (pintype "passive"))
      (node (ref "MSBOX5") (pin "15") (pinfunction "15_15") (pintype "passive"))
      (node (ref "MSBOX5") (pin "16") (pinfunction "16_16") (pintype "passive"))
      (node (ref "MSBOX5") (pin "2") (pinfunction "2_2") (pintype "passive"))
      (node (ref "MSBOX5") (pin "3") (pinfunction "3_3") (pintype "passive"))
      (node (ref "MSBOX5") (pin "4") (pinfunction "4_4") (pintype "passive"))
      (node (ref "MSBOX5") (pin "5") (pinfunction "5_5") (pintype "passive"))
      (node (ref "MSBOX5") (pin "6") (pinfunction "6_6") (pintype "passive"))
      (node (ref "MSBOX5") (pin "7") (pinfunction "7_7") (pintype "passive"))
      (node (ref "MSBOX5") (pin "8") (pinfunction "8_8") (pintype "passive"))
      (node (ref "MSBOX5") (pin "9") (pinfunction "9_9") (pintype "passive"))
      (node (ref "OSC1") (pin "2") (pinfunction "GND_2") (pintype "power_in"))
      (node (ref "R54") (pin "1") (pinfunction "1_1") (pintype "passive"))
      (node (ref "R55") (pin "1") (pinfunction "1_1") (pintype "passive"))
      (node (ref "R56") (pin "1") (pinfunction "1_1") (pintype "passive"))
      (node (ref "R57") (pin "1") (pinfunction "1_1") (pintype "passive"))
      (node (ref "R62") (pin "1") (pinfunction "1_1") (pintype "passive"))
      (node (ref "R63") (pin "1") (pinfunction "1_1") (pintype "passive"))
      (node (ref "R65") (pin "1") (pinfunction "1_1") (pintype "passive"))
      (node (ref "R66") (pin "1") (pinfunction "1_1") (pintype "passive"))
      (node (ref "R67") (pin "1") (pinfunction "1_1") (pintype "passive"))
      (node (ref "R68") (pin "1") (pinfunction "1_1") (pintype "passive"))
      (node (ref "R70") (pin "1") (pinfunction "1_1") (pintype "passive"))
      (node (ref "R71") (pin "1") (pinfunction "1_1") (pintype "passive"))
      (node (ref "R72") (pin "1") (pinfunction "1_1") (pintype "passive"))
      (node (ref "R73") (pin "1") (pinfunction "1_1") (pintype "passive"))
      (node (ref "R76") (pin "1") (pinfunction "1_1") (pintype "passive"))
      (node (ref "R79") (pin "1") (pinfunction "1_1") (pintype "passive"))
      (node (ref "R80") (pin "1") (pinfunction "1_1") (pintype "passive"))
      (node (ref "R81") (pin "1") (pinfunction "1_1") (pintype "passive"))
      (node (ref "R82") (pin "1") (pinfunction "1_1") (pintype "passive"))
      (node (ref "R87") (pin "2") (pinfunction "2_2") (pintype "passive"))
    )
    (net (code "70") (name "LMK00304_VDD") (class "Default")
      (node (ref "C166") (pin "2") (pinfunction "2_2") (pintype "passive"))
      (node (ref "C167") (pin "2") (pinfunction "2_2") (pintype "passive"))
      (node (ref "C168") (pin "2") (pinfunction "2_2") (pintype "passive"))
      (node (ref "C553") (pin "2") (pinfunction "2_2") (pintype "passive"))
      (node (ref "C554") (pin "2") (pinfunction "2_2") (pintype "passive"))
      (node (ref "C557") (pin "2") (pinfunction "2_2") (pintype "passive"))
      (node (ref "C558") (pin "2") (pinfunction "2_2") (pintype "passive"))
      (node (ref "IC9") (pin "10") (pinfunction "VCC_10") (pintype "power_in"))
      (node (ref "IC9") (pin "2") (pinfunction "VCCOA_2") (pintype "power_in"))
      (node (ref "IC9") (pin "20") (pinfunction "VCCOB_20") (pintype "power_in"))
      (node (ref "IC9") (pin "23") (pinfunction "VCCOB_23") (pintype "power_in"))
      (node (ref "IC9") (pin "28") (pinfunction "VCC_28") (pintype "power_in"))
      (node (ref "IC9") (pin "30") (pinfunction "VCCOC_30") (pintype "power_in"))
      (node (ref "IC9") (pin "5") (pinfunction "VCCOA_5") (pintype "power_in"))
      (node (ref "IC9") (pin "9") (pinfunction "CLKOUT_TYPE0_9") (pintype "output"))
      (node (ref "L20") (pin "2") (pinfunction "2_2") (pintype "passive"))
    )
    (net (code "71") (name "LMK00804_VDD") (class "Default")
      (node (ref "C171") (pin "2") (pinfunction "2_2") (pintype "passive"))
      (node (ref "C172") (pin "2") (pinfunction "2_2") (pintype "passive"))
      (node (ref "C173") (pin "2") (pinfunction "2_2") (pintype "passive"))
      (node (ref "IC10") (pin "11") (pinfunction "VDDO_11") (pintype "power_in"))
      (node (ref "IC10") (pin "15") (pinfunction "VDDO_15") (pintype "power_in"))
      (node (ref "IC10") (pin "2") (pinfunction "OE_2") (pintype "input"))
      (node (ref "IC10") (pin "3") (pinfunction "VDD_3") (pintype "power_in"))
      (node (ref "IC10") (pin "4") (pinfunction "CLK_EN_4") (pintype "input"))
      (node (ref "IC10") (pin "7") (pinfunction "CLK_SEL_7") (pintype "input"))
      (node (ref "L21") (pin "2") (pinfunction "2_2") (pintype "passive"))
    )
    (net (code "72") (name "Net-(C139-Pad2)") (class "Default")
      (node (ref "C139") (pin "2") (pinfunction "2_2") (pintype "passive"))
      (node (ref "R68") (pin "2") (pinfunction "2_2") (pintype "passive"))
    )
    (net (code "73") (name "Net-(C148-Pad1)") (class "Default")
      (node (ref "C148") (pin "1") (pinfunction "1_1") (pintype "passive"))
      (node (ref "R73") (pin "2") (pinfunction "2_2") (pintype "passive"))
    )
    (net (code "74") (name "Net-(C156-Pad1)") (class "Default")
      (node (ref "C156") (pin "1") (pinfunction "1_1") (pintype "passive"))
      (node (ref "R76") (pin "2") (pinfunction "2_2") (pintype "passive"))
    )
    (net (code "75") (name "Net-(C156-Pad2)") (class "Default")
      (node (ref "C156") (pin "2") (pinfunction "2_2") (pintype "passive"))
      (node (ref "C157") (pin "2") (pinfunction "2_2") (pintype "passive"))
      (node (ref "R74") (pin "2") (pinfunction "2_2") (pintype "passive"))
      (node (ref "R75") (pin "1") (pinfunction "1_1") (pintype "passive"))
    )
    (net (code "76") (name "Net-(DS1-C)") (class "Default")
      (node (ref "DS1") (pin "1") (pinfunction "C_1") (pintype "passive"))
      (node (ref "R87") (pin "1") (pinfunction "1_1") (pintype "passive"))
    )
    (net (code "77") (name "Net-(IC8-CLKUWIRE)") (class "Default")
      (node (ref "IC8") (pin "45") (pinfunction "CLKUWIRE_45") (pintype "input"))
      (node (ref "R59") (pin "1") (pinfunction "1_1") (pintype "passive"))
    )
    (net (code "78") (name "Net-(IC8-DATAUWIRE)") (class "Default")
      (node (ref "IC8") (pin "46") (pinfunction "DATAUWIRE_46") (pintype "input"))
      (node (ref "R60") (pin "1") (pinfunction "1_1") (pintype "passive"))
    )
    (net (code "79") (name "Net-(IC8-LDOBYP1)") (class "Default")
      (node (ref "C145") (pin "2") (pinfunction "2_2") (pintype "passive"))
      (node (ref "IC8") (pin "11") (pinfunction "LDOBYP1_11") (pintype "passive"))
    )
    (net (code "80") (name "Net-(IC8-LDOBYP2)") (class "Default")
      (node (ref "C146") (pin "2") (pinfunction "2_2") (pintype "passive"))
      (node (ref "IC8") (pin "12") (pinfunction "LDOBYP2_12") (pintype "passive"))
    )
    (net (code "81") (name "Net-(IC8-LEUWIRE)") (class "Default")
      (node (ref "IC8") (pin "44") (pinfunction "LEUWIRE_44") (pintype "input"))
      (node (ref "R58") (pin "1") (pinfunction "1_1") (pintype "passive"))
    )
    (net (code "82") (name "Net-(IC10-Q0)") (class "Default")
      (node (ref "IC10") (pin "16") (pinfunction "Q0_16") (pintype "output"))
      (node (ref "R83") (pin "1") (pinfunction "1_1") (pintype "passive"))
    )
    (net (code "83") (name "Net-(IC10-Q1)") (class "Default")
      (node (ref "IC10") (pin "14") (pinfunction "Q1_14") (pintype "output"))
      (node (ref "R84") (pin "1") (pinfunction "1_1") (pintype "passive"))
    )
    (net (code "84") (name "Net-(IC10-Q2)") (class "Default")
      (node (ref "IC10") (pin "12") (pinfunction "Q2_12") (pintype "output"))
      (node (ref "R85") (pin "1") (pinfunction "1_1") (pintype "passive"))
    )
    (net (code "85") (name "unconnected-(IC8-NC-Pad1)") (class "Default")
      (node (ref "IC8") (pin "1") (pinfunction "NC_1") (pintype "passive+no_connect"))
    )
    (net (code "86") (name "unconnected-(IC8-NC-Pad2)") (class "Default")
      (node (ref "IC8") (pin "2") (pinfunction "NC_2") (pintype "passive+no_connect"))
    )
    (net (code "87") (name "unconnected-(IC8-NC-Pad5)") (class "Default")
      (node (ref "IC8") (pin "5") (pinfunction "NC_5") (pintype "passive+no_connect"))
    )
    (net (code "88") (name "unconnected-(IC8-NC-Pad7)") (class "Default")
      (node (ref "IC8") (pin "7") (pinfunction "NC_7") (pintype "passive+no_connect"))
    )
    (net (code "89") (name "unconnected-(IC8-NC-Pad8)") (class "Default")
      (node (ref "IC8") (pin "8") (pinfunction "NC_8") (pintype "passive+no_connect"))
    )
    (net (code "90") (name "unconnected-(IC8-NC-Pad9)") (class "Default")
      (node (ref "IC8") (pin "9") (pinfunction "NC_9") (pintype "passive+no_connect"))
    )
    (net (code "91") (name "unconnected-(IC8-NC-Pad15)") (class "Default")
      (node (ref "IC8") (pin "15") (pinfunction "NC_15") (pintype "passive+no_connect"))
    )
    (net (code "92") (name "unconnected-(IC8-NC-Pad16)") (class "Default")
      (node (ref "IC8") (pin "16") (pinfunction "NC_16") (pintype "passive+no_connect"))
    )
    (net (code "93") (name "unconnected-(IC8-NC-Pad19)") (class "Default")
      (node (ref "IC8") (pin "19") (pinfunction "NC_19") (pintype "passive+no_connect"))
    )
    (net (code "94") (name "unconnected-(IC8-NC-Pad20)") (class "Default")
      (node (ref "IC8") (pin "20") (pinfunction "NC_20") (pintype "passive+no_connect"))
    )
    (net (code "95") (name "unconnected-(IC8-NC-Pad31)") (class "Default")
      (node (ref "IC8") (pin "31") (pinfunction "NC_31") (pintype "passive+no_connect"))
    )
    (net (code "96") (name "unconnected-(IC8-NC-Pad32)") (class "Default")
      (node (ref "IC8") (pin "32") (pinfunction "NC_32") (pintype "passive+no_connect"))
    )
    (net (code "97") (name "unconnected-(IC8-NC-Pad50)") (class "Default")
      (node (ref "IC8") (pin "50") (pinfunction "NC_50") (pintype "passive+no_connect"))
    )
    (net (code "98") (name "unconnected-(IC8-NC-Pad51)") (class "Default")
      (node (ref "IC8") (pin "51") (pinfunction "NC_51") (pintype "passive+no_connect"))
    )
    (net (code "99") (name "unconnected-(IC8-NC-Pad55)") (class "Default")
      (node (ref "IC8") (pin "55") (pinfunction "NC_55") (pintype "passive+no_connect"))
    )
    (net (code "100") (name "unconnected-(IC8-NC-Pad56)") (class "Default")
      (node (ref "IC8") (pin "56") (pinfunction "NC_56") (pintype "passive+no_connect"))
    )
    (net (code "101") (name "unconnected-(IC8-NC-Pad60)") (class "Default")
      (node (ref "IC8") (pin "60") (pinfunction "NC_60") (pintype "passive+no_connect"))
    )
    (net (code "102") (name "unconnected-(IC8-NC-Pad61)") (class "Default")
      (node (ref "IC8") (pin "61") (pinfunction "NC_61") (pintype "passive+no_connect"))
    )
    (net (code "103") (name "unconnected-(IC8-OSCOUT-Pad39)") (class "Default")
      (node (ref "IC8") (pin "39") (pinfunction "OSCOUT_39") (pintype "output+no_connect"))
    )
    (net (code "104") (name "unconnected-(IC8-STATUS_CLKIN0-Pad62)") (class "Default")
      (node (ref "IC8") (pin "62") (pinfunction "STATUS_CLKIN0_62") (pintype "bidirectional+no_connect"))
    )
    (net (code "105") (name "unconnected-(IC8-STATUS_CLKIN1-Pad63)") (class "Default")
      (node (ref "IC8") (pin "63") (pinfunction "STATUS_CLKIN1_63") (pintype "bidirectional+no_connect"))
    )
    (net (code "106") (name "unconnected-(IC8-SYNC-Pad6)") (class "Default")
      (node (ref "IC8") (pin "6") (pinfunction "SYNC_6") (pintype "bidirectional+no_connect"))
    )
    (net (code "107") (name "unconnected-(IC8-~{OSCOUT}-Pad40)") (class "Default")
      (node (ref "IC8") (pin "40") (pinfunction "~{OSCOUT}_40") (pintype "output+no_connect"))
    )
    (net (code "108") (name "unconnected-(IC9-CLKIN1-Pad27)") (class "Default")
      (node (ref "IC9") (pin "27") (pinfunction "CLKIN1_27") (pintype "input+no_connect"))
    )
    (net (code "109") (name "unconnected-(IC9-CLKOUTA0-Pad3)") (class "Default")
      (node (ref "IC9") (pin "3") (pinfunction "CLKOUTA0_3") (pintype "output+no_connect"))
    )
    (net (code "110") (name "unconnected-(IC9-NC-Pad25)") (class "Default")
      (node (ref "IC9") (pin "25") (pinfunction "NC_25") (pintype "passive+no_connect"))
    )
    (net (code "111") (name "unconnected-(IC9-OSCIN-Pad11)") (class "Default")
      (node (ref "IC9") (pin "11") (pinfunction "OSCIN_11") (pintype "input+no_connect"))
    )
    (net (code "112") (name "unconnected-(IC9-OSCOUT-Pad12)") (class "Default")
      (node (ref "IC9") (pin "12") (pinfunction "OSCOUT_12") (pintype "output+no_connect"))
    )
    (net (code "113") (name "unconnected-(IC9-REFOUT-Pad29)") (class "Default")
      (node (ref "IC9") (pin "29") (pinfunction "REFOUT_29") (pintype "output+no_connect"))
    )
    (net (code "114") (name "unconnected-(IC9-REFOUT_EN-Pad31)") (class "Default")
      (node (ref "IC9") (pin "31") (pinfunction "REFOUT_EN_31") (pintype "input+no_connect"))
    )
    (net (code "115") (name "unconnected-(IC9-~{CLKIN1}-Pad26)") (class "Default")
      (node (ref "IC9") (pin "26") (pinfunction "~{CLKIN1}_26") (pintype "input+no_connect"))
    )
    (net (code "116") (name "unconnected-(IC9-~{CLKOUTA0}-Pad4)") (class "Default")
      (node (ref "IC9") (pin "4") (pinfunction "~{CLKOUTA0}_4") (pintype "output+no_connect"))
    )
    (net (code "117") (name "unconnected-(IC10-LVCMOS_CLK-Pad8)") (class "Default")
      (node (ref "IC10") (pin "8") (pinfunction "LVCMOS_CLK_8") (pintype "input+no_connect"))
    )
    (net (code "118") (name "unconnected-(IC10-Q3-Pad10)") (class "Default")
      (node (ref "IC10") (pin "10") (pinfunction "Q3_10") (pintype "output"))
    )
  )
)
